# Sheet1.net
KiCad netlist of a schematic drawn in Altium Designer
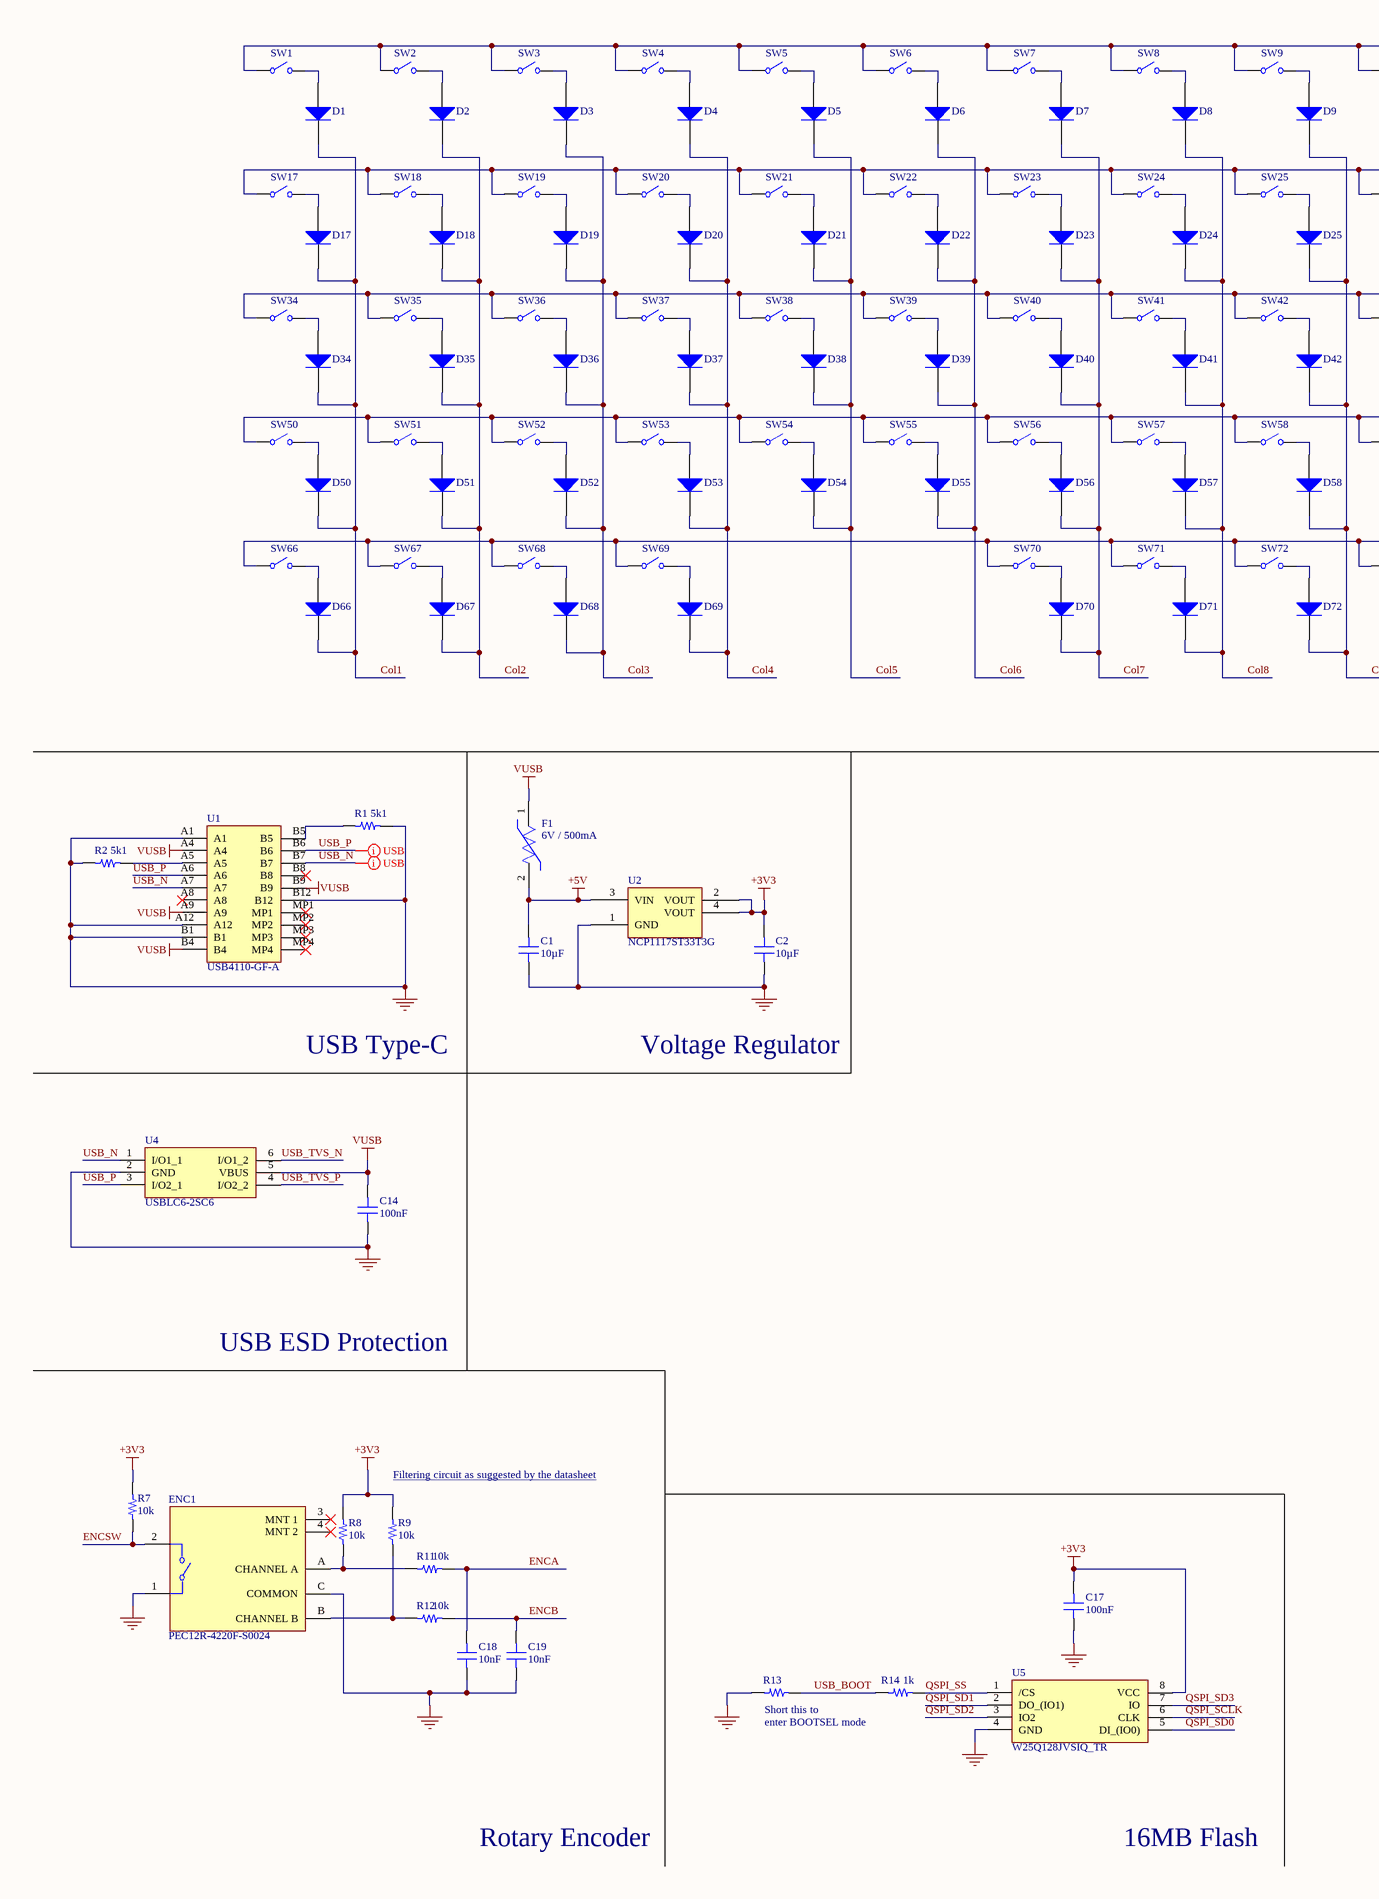
[diagram p0: Sheet1.SchDoc, left]
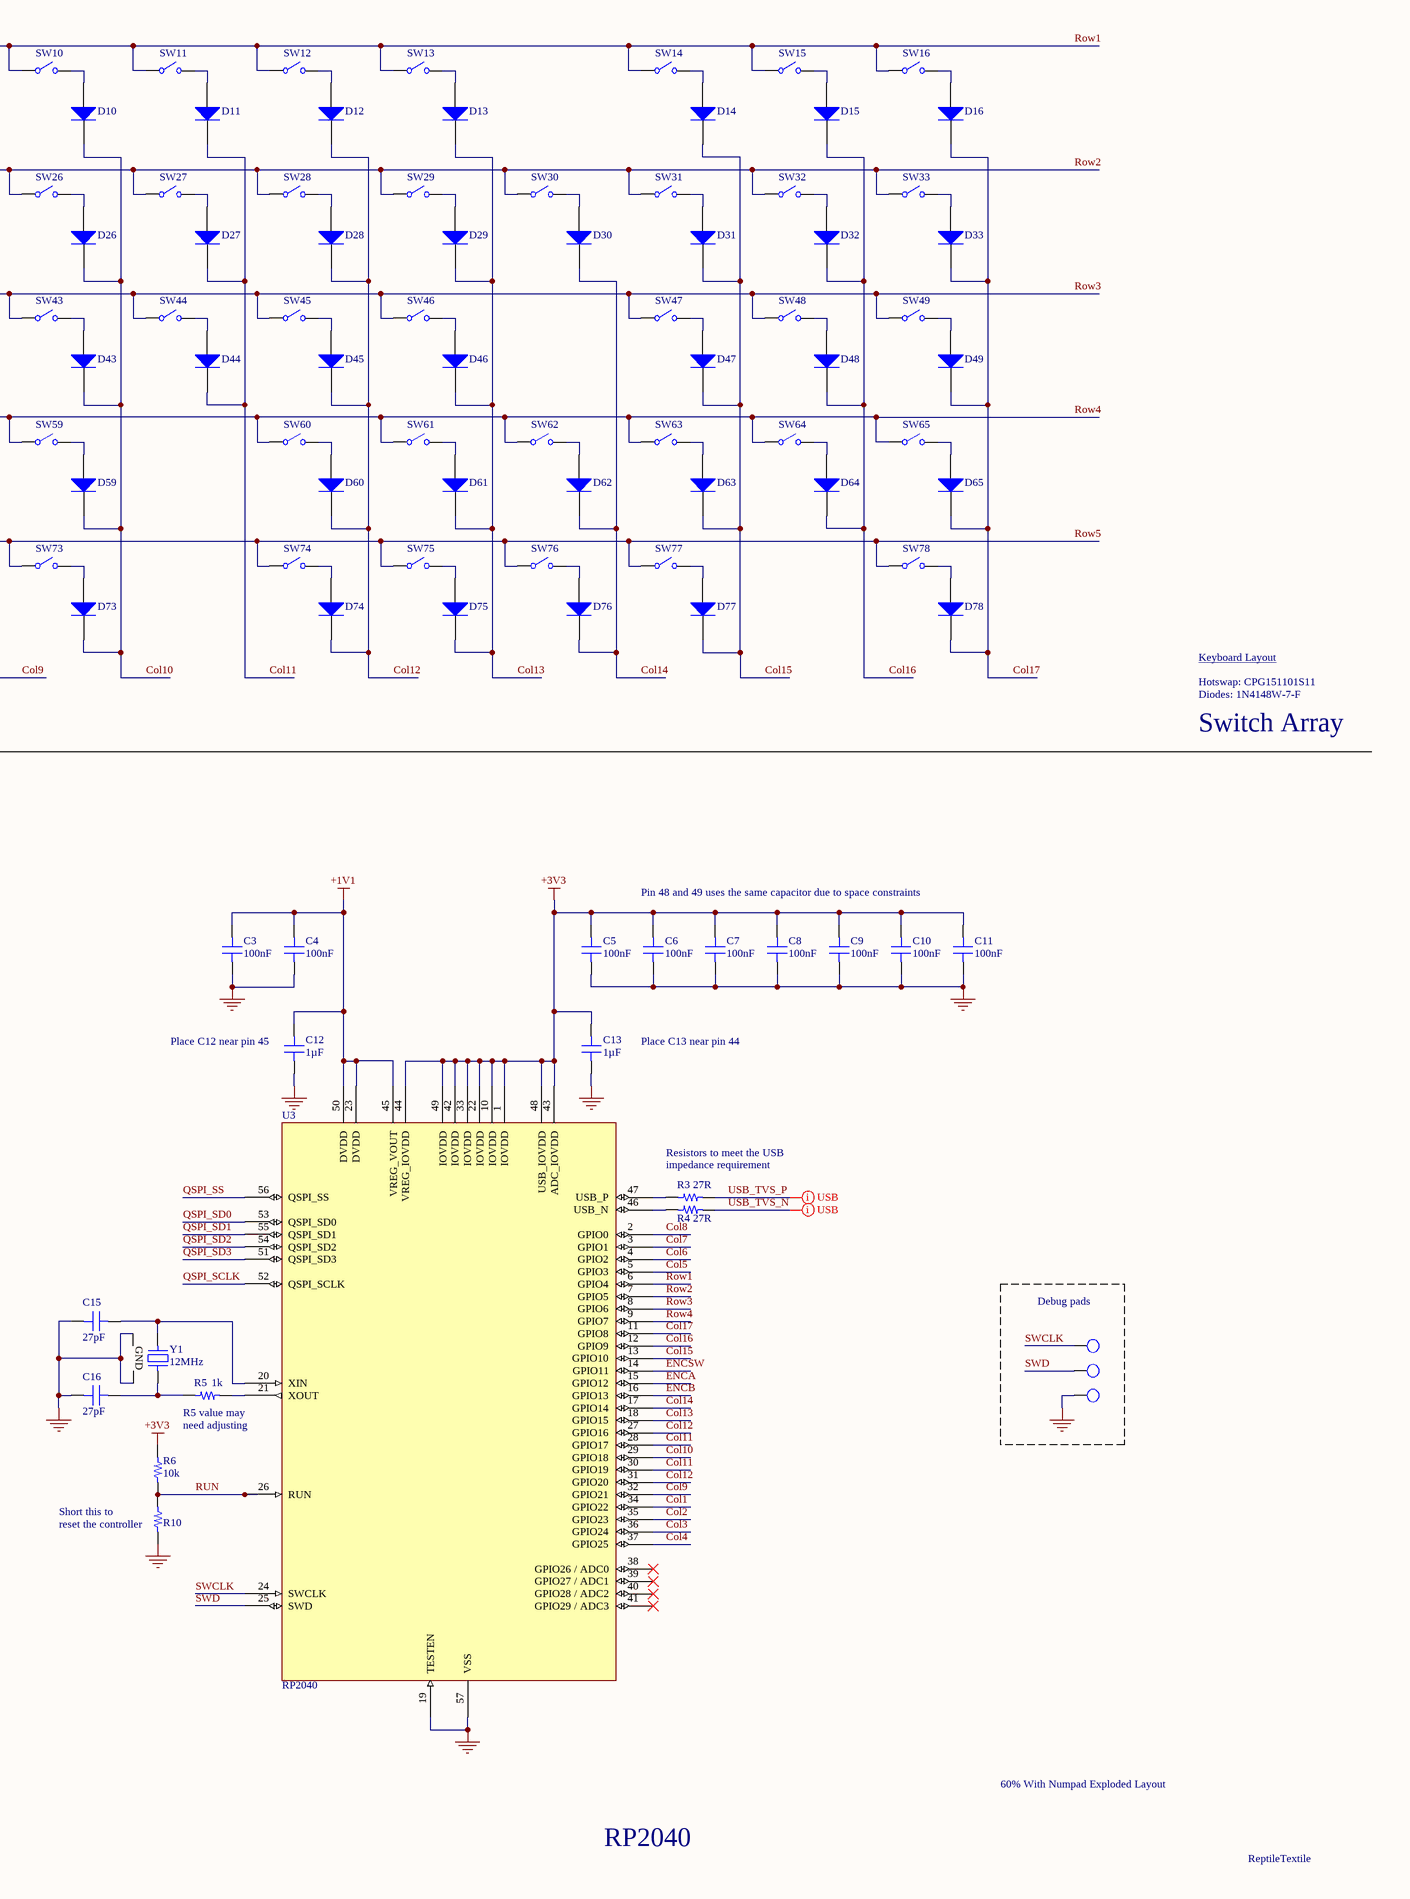
[diagram p1: Sheet1.SchDoc, right]

(export (version "E")
  (design (tool "Eeschema 10.0.6"))
  (components
    (comp (ref "C1")
      (value "10µF")
      (footprint "CAP 0402_1005")
      (description "CAP CER 10UF 10V X5R 0402")
      (fields
        (field (name "PART NUMBER") "CL05A106MP8NUB8")
        (field (name "MANUFACTURER") "Samsung Electro-Mechanics")
      )
      (libsource (lib "Celestial Altium Library") (part "Capacitor"))
    )
    (comp (ref "C2")
      (value "10µF")
      (footprint "CAP 0402_1005")
      (description "CAP CER 10UF 10V X5R 0402")
      (fields
        (field (name "PART NUMBER") "CL05A106MP8NUB8")
        (field (name "MANUFACTURER") "Samsung Electro-Mechanics")
      )
      (libsource (lib "Celestial Altium Library") (part "Capacitor"))
    )
    (comp (ref "C3")
      (value "100nF")
      (footprint "CAP 0402_1005")
      (description "CAP CER 0402 0.1UF 16V X7R 10%")
      (fields (field (name "PART NUMBER") "C0402C104K4RECAUTO") (field (name "MANUFACTURER") "KEMET"))
      (libsource (lib "Celestial Altium Library") (part "Capacitor"))
    )
    (comp (ref "C4")
      (value "100nF")
      (footprint "CAP 0402_1005")
      (description "CAP CER 0402 0.1UF 16V X7R 10%")
      (fields (field (name "PART NUMBER") "C0402C104K4RECAUTO") (field (name "MANUFACTURER") "KEMET"))
      (libsource (lib "Celestial Altium Library") (part "Capacitor"))
    )
    (comp (ref "C5")
      (value "100nF")
      (footprint "CAP 0402_1005")
      (description "CAP CER 0402 0.1UF 16V X7R 10%")
      (fields (field (name "PART NUMBER") "C0402C104K4RECAUTO") (field (name "MANUFACTURER") "KEMET"))
      (libsource (lib "Celestial Altium Library") (part "Capacitor"))
    )
    (comp (ref "C6")
      (value "100nF")
      (footprint "CAP 0402_1005")
      (description "CAP CER 0402 0.1UF 16V X7R 10%")
      (fields (field (name "PART NUMBER") "C0402C104K4RECAUTO") (field (name "MANUFACTURER") "KEMET"))
      (libsource (lib "Celestial Altium Library") (part "Capacitor"))
    )
    (comp (ref "C7")
      (value "100nF")
      (footprint "CAP 0402_1005")
      (description "CAP CER 0402 0.1UF 16V X7R 10%")
      (fields (field (name "PART NUMBER") "C0402C104K4RECAUTO") (field (name "MANUFACTURER") "KEMET"))
      (libsource (lib "Celestial Altium Library") (part "Capacitor"))
    )
    (comp (ref "C8")
      (value "100nF")
      (footprint "CAP 0402_1005")
      (description "CAP CER 0402 0.1UF 16V X7R 10%")
      (fields (field (name "PART NUMBER") "C0402C104K4RECAUTO") (field (name "MANUFACTURER") "KEMET"))
      (libsource (lib "Celestial Altium Library") (part "Capacitor"))
    )
    (comp (ref "C9")
      (value "100nF")
      (footprint "CAP 0402_1005")
      (description "CAP CER 0402 0.1UF 16V X7R 10%")
      (fields (field (name "PART NUMBER") "C0402C104K4RECAUTO") (field (name "MANUFACTURER") "KEMET"))
      (libsource (lib "Celestial Altium Library") (part "Capacitor"))
    )
    (comp (ref "C10")
      (value "100nF")
      (footprint "CAP 0402_1005")
      (description "CAP CER 0402 0.1UF 16V X7R 10%")
      (fields (field (name "PART NUMBER") "C0402C104K4RECAUTO") (field (name "MANUFACTURER") "KEMET"))
      (libsource (lib "Celestial Altium Library") (part "Capacitor"))
    )
    (comp (ref "C11")
      (value "100nF")
      (footprint "CAP 0402_1005")
      (description "CAP CER 0402 0.1UF 16V X7R 10%")
      (fields (field (name "PART NUMBER") "C0402C104K4RECAUTO") (field (name "MANUFACTURER") "KEMET"))
      (libsource (lib "Celestial Altium Library") (part "Capacitor"))
    )
    (comp (ref "C12")
      (value "1µF")
      (footprint "CAP 0402_1005")
      (description "CAP CER 1UF 10V X7S 0402")
      (fields
        (field (name "PART NUMBER") "GRM155C71A105KE11D")
        (field (name "MANUFACTURER") "Murata Electronics")
      )
      (libsource (lib "Celestial Altium Library") (part "Capacitor"))
    )
    (comp (ref "C13")
      (value "1µF")
      (footprint "CAP 0402_1005")
      (description "CAP CER 1UF 10V X7S 0402")
      (fields
        (field (name "PART NUMBER") "GRM155C71A105KE11D")
        (field (name "MANUFACTURER") "Murata Electronics")
      )
      (libsource (lib "Celestial Altium Library") (part "Capacitor"))
    )
    (comp (ref "C14")
      (value "100nF")
      (footprint "CAP 0402_1005")
      (description "CAP CER 0402 0.1UF 16V X7R 10%")
      (fields (field (name "PART NUMBER") "C0402C104K4RECAUTO") (field (name "MANUFACTURER") "KEMET"))
      (libsource (lib "Celestial Altium Library") (part "Capacitor"))
    )
    (comp (ref "C15")
      (value "27pF")
      (footprint "CAP 0402_1005")
      (description "CAP CER 27PF 25V NP0 0402")
      (fields (field (name "PART NUMBER") "C0402C270J3GAC7867") (field (name "MANUFACTURER") "KEMET"))
      (libsource (lib "Celestial Altium Library") (part "Capacitor"))
    )
    (comp (ref "C16")
      (value "27pF")
      (footprint "CAP 0402_1005")
      (description "CAP CER 27PF 25V NP0 0402")
      (fields (field (name "PART NUMBER") "C0402C270J3GAC7867") (field (name "MANUFACTURER") "KEMET"))
      (libsource (lib "Celestial Altium Library") (part "Capacitor"))
    )
    (comp (ref "C17")
      (value "100nF")
      (footprint "CAP 0402_1005")
      (description "CAP CER 0402 0.1UF 16V X7R 10%")
      (fields (field (name "PART NUMBER") "C0402C104K4RECAUTO") (field (name "MANUFACTURER") "KEMET"))
      (libsource (lib "Celestial Altium Library") (part "Capacitor"))
    )
    (comp (ref "C18")
      (value "10nF")
      (footprint "CAP 0402_1005")
      (description "CAP CER 0402 10NF 50V X7R 5%")
      (fields (field (name "PART NUMBER") "C0402C103J5RECAUTO") (field (name "MANUFACTURER") "KEMET"))
      (libsource (lib "Celestial Altium Library") (part "Capacitor"))
    )
    (comp (ref "C19")
      (value "10nF")
      (footprint "CAP 0402_1005")
      (description "CAP CER 0402 10NF 50V X7R 5%")
      (fields (field (name "PART NUMBER") "C0402C103J5RECAUTO") (field (name "MANUFACTURER") "KEMET"))
      (libsource (lib "Celestial Altium Library") (part "Capacitor"))
    )
    (comp (ref "D1")
      (value "1N4148W-7-F")
      (footprint "DIOD-SOD123-2_V")
      (description "Fast Switching Diode, 100 V, 0.15 A, -65 to 150 degC, 2-Pin?SOD123, RoHS, Tape and Reel")
      (fields (field (name "MANUFACTURER") "DiodesIncorporated"))
      (libsource (lib "Altium Content Vault") (part "D-AK-2"))
    )
    (comp (ref "D2")
      (value "1N4148W-7-F")
      (footprint "DIOD-SOD123-2_V")
      (description "Fast Switching Diode, 100 V, 0.15 A, -65 to 150 degC, 2-Pin?SOD123, RoHS, Tape and Reel")
      (fields (field (name "MANUFACTURER") "DiodesIncorporated"))
      (libsource (lib "Altium Content Vault") (part "D-AK-2"))
    )
    (comp (ref "D3")
      (value "1N4148W-7-F")
      (footprint "DIOD-SOD123-2_V")
      (description "Fast Switching Diode, 100 V, 0.15 A, -65 to 150 degC, 2-Pin?SOD123, RoHS, Tape and Reel")
      (fields (field (name "MANUFACTURER") "DiodesIncorporated"))
      (libsource (lib "Altium Content Vault") (part "D-AK-2"))
    )
    (comp (ref "D4")
      (value "1N4148W-7-F")
      (footprint "DIOD-SOD123-2_V")
      (description "Fast Switching Diode, 100 V, 0.15 A, -65 to 150 degC, 2-Pin?SOD123, RoHS, Tape and Reel")
      (fields (field (name "MANUFACTURER") "DiodesIncorporated"))
      (libsource (lib "Altium Content Vault") (part "D-AK-2"))
    )
    (comp (ref "D5")
      (value "1N4148W-7-F")
      (footprint "DIOD-SOD123-2_V")
      (description "Fast Switching Diode, 100 V, 0.15 A, -65 to 150 degC, 2-Pin?SOD123, RoHS, Tape and Reel")
      (fields (field (name "MANUFACTURER") "DiodesIncorporated"))
      (libsource (lib "Altium Content Vault") (part "D-AK-2"))
    )
    (comp (ref "D6")
      (value "1N4148W-7-F")
      (footprint "DIOD-SOD123-2_V")
      (description "Fast Switching Diode, 100 V, 0.15 A, -65 to 150 degC, 2-Pin?SOD123, RoHS, Tape and Reel")
      (fields (field (name "MANUFACTURER") "DiodesIncorporated"))
      (libsource (lib "Altium Content Vault") (part "D-AK-2"))
    )
    (comp (ref "D7")
      (value "1N4148W-7-F")
      (footprint "DIOD-SOD123-2_V")
      (description "Fast Switching Diode, 100 V, 0.15 A, -65 to 150 degC, 2-Pin?SOD123, RoHS, Tape and Reel")
      (fields (field (name "MANUFACTURER") "DiodesIncorporated"))
      (libsource (lib "Altium Content Vault") (part "D-AK-2"))
    )
    (comp (ref "D8")
      (value "1N4148W-7-F")
      (footprint "DIOD-SOD123-2_V")
      (description "Fast Switching Diode, 100 V, 0.15 A, -65 to 150 degC, 2-Pin?SOD123, RoHS, Tape and Reel")
      (fields (field (name "MANUFACTURER") "DiodesIncorporated"))
      (libsource (lib "Altium Content Vault") (part "D-AK-2"))
    )
    (comp (ref "D9")
      (value "1N4148W-7-F")
      (footprint "DIOD-SOD123-2_V")
      (description "Fast Switching Diode, 100 V, 0.15 A, -65 to 150 degC, 2-Pin?SOD123, RoHS, Tape and Reel")
      (fields (field (name "MANUFACTURER") "DiodesIncorporated"))
      (libsource (lib "Altium Content Vault") (part "D-AK-2"))
    )
    (comp (ref "D10")
      (value "1N4148W-7-F")
      (footprint "DIOD-SOD123-2_V")
      (description "Fast Switching Diode, 100 V, 0.15 A, -65 to 150 degC, 2-Pin?SOD123, RoHS, Tape and Reel")
      (fields (field (name "MANUFACTURER") "DiodesIncorporated"))
      (libsource (lib "Altium Content Vault") (part "D-AK-2"))
    )
    (comp (ref "D11")
      (value "1N4148W-7-F")
      (footprint "DIOD-SOD123-2_V")
      (description "Fast Switching Diode, 100 V, 0.15 A, -65 to 150 degC, 2-Pin?SOD123, RoHS, Tape and Reel")
      (fields (field (name "MANUFACTURER") "DiodesIncorporated"))
      (libsource (lib "Altium Content Vault") (part "D-AK-2"))
    )
    (comp (ref "D12")
      (value "1N4148W-7-F")
      (footprint "DIOD-SOD123-2_V")
      (description "Fast Switching Diode, 100 V, 0.15 A, -65 to 150 degC, 2-Pin?SOD123, RoHS, Tape and Reel")
      (fields (field (name "MANUFACTURER") "DiodesIncorporated"))
      (libsource (lib "Altium Content Vault") (part "D-AK-2"))
    )
    (comp (ref "D13")
      (value "1N4148W-7-F")
      (footprint "DIOD-SOD123-2_V")
      (description "Fast Switching Diode, 100 V, 0.15 A, -65 to 150 degC, 2-Pin?SOD123, RoHS, Tape and Reel")
      (fields (field (name "MANUFACTURER") "DiodesIncorporated"))
      (libsource (lib "Altium Content Vault") (part "D-AK-2"))
    )
    (comp (ref "D14")
      (value "1N4148W-7-F")
      (footprint "DIOD-SOD123-2_V")
      (description "Fast Switching Diode, 100 V, 0.15 A, -65 to 150 degC, 2-Pin?SOD123, RoHS, Tape and Reel")
      (fields (field (name "MANUFACTURER") "DiodesIncorporated"))
      (libsource (lib "Altium Content Vault") (part "D-AK-2"))
    )
    (comp (ref "D15")
      (value "1N4148W-7-F")
      (footprint "DIOD-SOD123-2_V")
      (description "Fast Switching Diode, 100 V, 0.15 A, -65 to 150 degC, 2-Pin?SOD123, RoHS, Tape and Reel")
      (fields (field (name "MANUFACTURER") "DiodesIncorporated"))
      (libsource (lib "Altium Content Vault") (part "D-AK-2"))
    )
    (comp (ref "D16")
      (value "1N4148W-7-F")
      (footprint "DIOD-SOD123-2_V")
      (description "Fast Switching Diode, 100 V, 0.15 A, -65 to 150 degC, 2-Pin?SOD123, RoHS, Tape and Reel")
      (fields (field (name "MANUFACTURER") "DiodesIncorporated"))
      (libsource (lib "Altium Content Vault") (part "D-AK-2"))
    )
    (comp (ref "D17")
      (value "1N4148W-7-F")
      (footprint "DIOD-SOD123-2_V")
      (description "Fast Switching Diode, 100 V, 0.15 A, -65 to 150 degC, 2-Pin?SOD123, RoHS, Tape and Reel")
      (fields (field (name "MANUFACTURER") "DiodesIncorporated"))
      (libsource (lib "Altium Content Vault") (part "D-AK-2"))
    )
    (comp (ref "D18")
      (value "1N4148W-7-F")
      (footprint "DIOD-SOD123-2_V")
      (description "Fast Switching Diode, 100 V, 0.15 A, -65 to 150 degC, 2-Pin?SOD123, RoHS, Tape and Reel")
      (fields (field (name "MANUFACTURER") "DiodesIncorporated"))
      (libsource (lib "Altium Content Vault") (part "D-AK-2"))
    )
    (comp (ref "D19")
      (value "1N4148W-7-F")
      (footprint "DIOD-SOD123-2_V")
      (description "Fast Switching Diode, 100 V, 0.15 A, -65 to 150 degC, 2-Pin?SOD123, RoHS, Tape and Reel")
      (fields (field (name "MANUFACTURER") "DiodesIncorporated"))
      (libsource (lib "Altium Content Vault") (part "D-AK-2"))
    )
    (comp (ref "D20")
      (value "1N4148W-7-F")
      (footprint "DIOD-SOD123-2_V")
      (description "Fast Switching Diode, 100 V, 0.15 A, -65 to 150 degC, 2-Pin?SOD123, RoHS, Tape and Reel")
      (fields (field (name "MANUFACTURER") "DiodesIncorporated"))
      (libsource (lib "Altium Content Vault") (part "D-AK-2"))
    )
    (comp (ref "D21")
      (value "1N4148W-7-F")
      (footprint "DIOD-SOD123-2_V")
      (description "Fast Switching Diode, 100 V, 0.15 A, -65 to 150 degC, 2-Pin?SOD123, RoHS, Tape and Reel")
      (fields (field (name "MANUFACTURER") "DiodesIncorporated"))
      (libsource (lib "Altium Content Vault") (part "D-AK-2"))
    )
    (comp (ref "D22")
      (value "1N4148W-7-F")
      (footprint "DIOD-SOD123-2_V")
      (description "Fast Switching Diode, 100 V, 0.15 A, -65 to 150 degC, 2-Pin?SOD123, RoHS, Tape and Reel")
      (fields (field (name "MANUFACTURER") "DiodesIncorporated"))
      (libsource (lib "Altium Content Vault") (part "D-AK-2"))
    )
    (comp (ref "D23")
      (value "1N4148W-7-F")
      (footprint "DIOD-SOD123-2_V")
      (description "Fast Switching Diode, 100 V, 0.15 A, -65 to 150 degC, 2-Pin?SOD123, RoHS, Tape and Reel")
      (fields (field (name "MANUFACTURER") "DiodesIncorporated"))
      (libsource (lib "Altium Content Vault") (part "D-AK-2"))
    )
    (comp (ref "D24")
      (value "1N4148W-7-F")
      (footprint "DIOD-SOD123-2_V")
      (description "Fast Switching Diode, 100 V, 0.15 A, -65 to 150 degC, 2-Pin?SOD123, RoHS, Tape and Reel")
      (fields (field (name "MANUFACTURER") "DiodesIncorporated"))
      (libsource (lib "Altium Content Vault") (part "D-AK-2"))
    )
    (comp (ref "D25")
      (value "1N4148W-7-F")
      (footprint "DIOD-SOD123-2_V")
      (description "Fast Switching Diode, 100 V, 0.15 A, -65 to 150 degC, 2-Pin?SOD123, RoHS, Tape and Reel")
      (fields (field (name "MANUFACTURER") "DiodesIncorporated"))
      (libsource (lib "Altium Content Vault") (part "D-AK-2"))
    )
    (comp (ref "D26")
      (value "1N4148W-7-F")
      (footprint "DIOD-SOD123-2_V")
      (description "Fast Switching Diode, 100 V, 0.15 A, -65 to 150 degC, 2-Pin?SOD123, RoHS, Tape and Reel")
      (fields (field (name "MANUFACTURER") "DiodesIncorporated"))
      (libsource (lib "Altium Content Vault") (part "D-AK-2"))
    )
    (comp (ref "D27")
      (value "1N4148W-7-F")
      (footprint "DIOD-SOD123-2_V")
      (description "Fast Switching Diode, 100 V, 0.15 A, -65 to 150 degC, 2-Pin?SOD123, RoHS, Tape and Reel")
      (fields (field (name "MANUFACTURER") "DiodesIncorporated"))
      (libsource (lib "Altium Content Vault") (part "D-AK-2"))
    )
    (comp (ref "D28")
      (value "1N4148W-7-F")
      (footprint "DIOD-SOD123-2_V")
      (description "Fast Switching Diode, 100 V, 0.15 A, -65 to 150 degC, 2-Pin?SOD123, RoHS, Tape and Reel")
      (fields (field (name "MANUFACTURER") "DiodesIncorporated"))
      (libsource (lib "Altium Content Vault") (part "D-AK-2"))
    )
    (comp (ref "D29")
      (value "1N4148W-7-F")
      (footprint "DIOD-SOD123-2_V")
      (description "Fast Switching Diode, 100 V, 0.15 A, -65 to 150 degC, 2-Pin?SOD123, RoHS, Tape and Reel")
      (fields (field (name "MANUFACTURER") "DiodesIncorporated"))
      (libsource (lib "Altium Content Vault") (part "D-AK-2"))
    )
    (comp (ref "D30")
      (value "1N4148W-7-F")
      (footprint "DIOD-SOD123-2_V")
      (description "Fast Switching Diode, 100 V, 0.15 A, -65 to 150 degC, 2-Pin?SOD123, RoHS, Tape and Reel")
      (fields (field (name "MANUFACTURER") "DiodesIncorporated"))
      (libsource (lib "Altium Content Vault") (part "D-AK-2"))
    )
    (comp (ref "D31")
      (value "1N4148W-7-F")
      (footprint "DIOD-SOD123-2_V")
      (description "Fast Switching Diode, 100 V, 0.15 A, -65 to 150 degC, 2-Pin?SOD123, RoHS, Tape and Reel")
      (fields (field (name "MANUFACTURER") "DiodesIncorporated"))
      (libsource (lib "Altium Content Vault") (part "D-AK-2"))
    )
    (comp (ref "D32")
      (value "1N4148W-7-F")
      (footprint "DIOD-SOD123-2_V")
      (description "Fast Switching Diode, 100 V, 0.15 A, -65 to 150 degC, 2-Pin?SOD123, RoHS, Tape and Reel")
      (fields (field (name "MANUFACTURER") "DiodesIncorporated"))
      (libsource (lib "Altium Content Vault") (part "D-AK-2"))
    )
    (comp (ref "D33")
      (value "1N4148W-7-F")
      (footprint "DIOD-SOD123-2_V")
      (description "Fast Switching Diode, 100 V, 0.15 A, -65 to 150 degC, 2-Pin?SOD123, RoHS, Tape and Reel")
      (fields (field (name "MANUFACTURER") "DiodesIncorporated"))
      (libsource (lib "Altium Content Vault") (part "D-AK-2"))
    )
    (comp (ref "D34")
      (value "1N4148W-7-F")
      (footprint "DIOD-SOD123-2_V")
      (description "Fast Switching Diode, 100 V, 0.15 A, -65 to 150 degC, 2-Pin?SOD123, RoHS, Tape and Reel")
      (fields (field (name "MANUFACTURER") "DiodesIncorporated"))
      (libsource (lib "Altium Content Vault") (part "D-AK-2"))
    )
    (comp (ref "D35")
      (value "1N4148W-7-F")
      (footprint "DIOD-SOD123-2_V")
      (description "Fast Switching Diode, 100 V, 0.15 A, -65 to 150 degC, 2-Pin?SOD123, RoHS, Tape and Reel")
      (fields (field (name "MANUFACTURER") "DiodesIncorporated"))
      (libsource (lib "Altium Content Vault") (part "D-AK-2"))
    )
    (comp (ref "D36")
      (value "1N4148W-7-F")
      (footprint "DIOD-SOD123-2_V")
      (description "Fast Switching Diode, 100 V, 0.15 A, -65 to 150 degC, 2-Pin?SOD123, RoHS, Tape and Reel")
      (fields (field (name "MANUFACTURER") "DiodesIncorporated"))
      (libsource (lib "Altium Content Vault") (part "D-AK-2"))
    )
    (comp (ref "D37")
      (value "1N4148W-7-F")
      (footprint "DIOD-SOD123-2_V")
      (description "Fast Switching Diode, 100 V, 0.15 A, -65 to 150 degC, 2-Pin?SOD123, RoHS, Tape and Reel")
      (fields (field (name "MANUFACTURER") "DiodesIncorporated"))
      (libsource (lib "Altium Content Vault") (part "D-AK-2"))
    )
    (comp (ref "D38")
      (value "1N4148W-7-F")
      (footprint "DIOD-SOD123-2_V")
      (description "Fast Switching Diode, 100 V, 0.15 A, -65 to 150 degC, 2-Pin?SOD123, RoHS, Tape and Reel")
      (fields (field (name "MANUFACTURER") "DiodesIncorporated"))
      (libsource (lib "Altium Content Vault") (part "D-AK-2"))
    )
    (comp (ref "D39")
      (value "1N4148W-7-F")
      (footprint "DIOD-SOD123-2_V")
      (description "Fast Switching Diode, 100 V, 0.15 A, -65 to 150 degC, 2-Pin?SOD123, RoHS, Tape and Reel")
      (fields (field (name "MANUFACTURER") "DiodesIncorporated"))
      (libsource (lib "Altium Content Vault") (part "D-AK-2"))
    )
    (comp (ref "D40")
      (value "1N4148W-7-F")
      (footprint "DIOD-SOD123-2_V")
      (description "Fast Switching Diode, 100 V, 0.15 A, -65 to 150 degC, 2-Pin?SOD123, RoHS, Tape and Reel")
      (fields (field (name "MANUFACTURER") "DiodesIncorporated"))
      (libsource (lib "Altium Content Vault") (part "D-AK-2"))
    )
    (comp (ref "D41")
      (value "1N4148W-7-F")
      (footprint "DIOD-SOD123-2_V")
      (description "Fast Switching Diode, 100 V, 0.15 A, -65 to 150 degC, 2-Pin?SOD123, RoHS, Tape and Reel")
      (fields (field (name "MANUFACTURER") "DiodesIncorporated"))
      (libsource (lib "Altium Content Vault") (part "D-AK-2"))
    )
    (comp (ref "D42")
      (value "1N4148W-7-F")
      (footprint "DIOD-SOD123-2_V")
      (description "Fast Switching Diode, 100 V, 0.15 A, -65 to 150 degC, 2-Pin?SOD123, RoHS, Tape and Reel")
      (fields (field (name "MANUFACTURER") "DiodesIncorporated"))
      (libsource (lib "Altium Content Vault") (part "D-AK-2"))
    )
    (comp (ref "D43")
      (value "1N4148W-7-F")
      (footprint "DIOD-SOD123-2_V")
      (description "Fast Switching Diode, 100 V, 0.15 A, -65 to 150 degC, 2-Pin?SOD123, RoHS, Tape and Reel")
      (fields (field (name "MANUFACTURER") "DiodesIncorporated"))
      (libsource (lib "Altium Content Vault") (part "D-AK-2"))
    )
    (comp (ref "D44")
      (value "1N4148W-7-F")
      (footprint "DIOD-SOD123-2_V")
      (description "Fast Switching Diode, 100 V, 0.15 A, -65 to 150 degC, 2-Pin?SOD123, RoHS, Tape and Reel")
      (fields (field (name "MANUFACTURER") "DiodesIncorporated"))
      (libsource (lib "Altium Content Vault") (part "D-AK-2"))
    )
    (comp (ref "D45")
      (value "1N4148W-7-F")
      (footprint "DIOD-SOD123-2_V")
      (description "Fast Switching Diode, 100 V, 0.15 A, -65 to 150 degC, 2-Pin?SOD123, RoHS, Tape and Reel")
      (fields (field (name "MANUFACTURER") "DiodesIncorporated"))
      (libsource (lib "Altium Content Vault") (part "D-AK-2"))
    )
    (comp (ref "D46")
      (value "1N4148W-7-F")
      (footprint "DIOD-SOD123-2_V")
      (description "Fast Switching Diode, 100 V, 0.15 A, -65 to 150 degC, 2-Pin?SOD123, RoHS, Tape and Reel")
      (fields (field (name "MANUFACTURER") "DiodesIncorporated"))
      (libsource (lib "Altium Content Vault") (part "D-AK-2"))
    )
    (comp (ref "D47")
      (value "1N4148W-7-F")
      (footprint "DIOD-SOD123-2_V")
      (description "Fast Switching Diode, 100 V, 0.15 A, -65 to 150 degC, 2-Pin?SOD123, RoHS, Tape and Reel")
      (fields (field (name "MANUFACTURER") "DiodesIncorporated"))
      (libsource (lib "Altium Content Vault") (part "D-AK-2"))
    )
    (comp (ref "D48")
      (value "1N4148W-7-F")
      (footprint "DIOD-SOD123-2_V")
      (description "Fast Switching Diode, 100 V, 0.15 A, -65 to 150 degC, 2-Pin?SOD123, RoHS, Tape and Reel")
      (fields (field (name "MANUFACTURER") "DiodesIncorporated"))
      (libsource (lib "Altium Content Vault") (part "D-AK-2"))
    )
    (comp (ref "D49")
      (value "1N4148W-7-F")
      (footprint "DIOD-SOD123-2_V")
      (description "Fast Switching Diode, 100 V, 0.15 A, -65 to 150 degC, 2-Pin?SOD123, RoHS, Tape and Reel")
      (fields (field (name "MANUFACTURER") "DiodesIncorporated"))
      (libsource (lib "Altium Content Vault") (part "D-AK-2"))
    )
    (comp (ref "D50")
      (value "1N4148W-7-F")
      (footprint "DIOD-SOD123-2_V")
      (description "Fast Switching Diode, 100 V, 0.15 A, -65 to 150 degC, 2-Pin?SOD123, RoHS, Tape and Reel")
      (fields (field (name "MANUFACTURER") "DiodesIncorporated"))
      (libsource (lib "Altium Content Vault") (part "D-AK-2"))
    )
    (comp (ref "D51")
      (value "1N4148W-7-F")
      (footprint "DIOD-SOD123-2_V")
      (description "Fast Switching Diode, 100 V, 0.15 A, -65 to 150 degC, 2-Pin?SOD123, RoHS, Tape and Reel")
      (fields (field (name "MANUFACTURER") "DiodesIncorporated"))
      (libsource (lib "Altium Content Vault") (part "D-AK-2"))
    )
    (comp (ref "D52")
      (value "1N4148W-7-F")
      (footprint "DIOD-SOD123-2_V")
      (description "Fast Switching Diode, 100 V, 0.15 A, -65 to 150 degC, 2-Pin?SOD123, RoHS, Tape and Reel")
      (fields (field (name "MANUFACTURER") "DiodesIncorporated"))
      (libsource (lib "Altium Content Vault") (part "D-AK-2"))
    )
    (comp (ref "D53")
      (value "1N4148W-7-F")
      (footprint "DIOD-SOD123-2_V")
      (description "Fast Switching Diode, 100 V, 0.15 A, -65 to 150 degC, 2-Pin?SOD123, RoHS, Tape and Reel")
      (fields (field (name "MANUFACTURER") "DiodesIncorporated"))
      (libsource (lib "Altium Content Vault") (part "D-AK-2"))
    )
    (comp (ref "D54")
      (value "1N4148W-7-F")
      (footprint "DIOD-SOD123-2_V")
      (description "Fast Switching Diode, 100 V, 0.15 A, -65 to 150 degC, 2-Pin?SOD123, RoHS, Tape and Reel")
      (fields (field (name "MANUFACTURER") "DiodesIncorporated"))
      (libsource (lib "Altium Content Vault") (part "D-AK-2"))
    )
    (comp (ref "D55")
      (value "1N4148W-7-F")
      (footprint "DIOD-SOD123-2_V")
      (description "Fast Switching Diode, 100 V, 0.15 A, -65 to 150 degC, 2-Pin?SOD123, RoHS, Tape and Reel")
      (fields (field (name "MANUFACTURER") "DiodesIncorporated"))
      (libsource (lib "Altium Content Vault") (part "D-AK-2"))
    )
    (comp (ref "D56")
      (value "1N4148W-7-F")
      (footprint "DIOD-SOD123-2_V")
      (description "Fast Switching Diode, 100 V, 0.15 A, -65 to 150 degC, 2-Pin?SOD123, RoHS, Tape and Reel")
      (fields (field (name "MANUFACTURER") "DiodesIncorporated"))
      (libsource (lib "Altium Content Vault") (part "D-AK-2"))
    )
    (comp (ref "D57")
      (value "1N4148W-7-F")
      (footprint "DIOD-SOD123-2_V")
      (description "Fast Switching Diode, 100 V, 0.15 A, -65 to 150 degC, 2-Pin?SOD123, RoHS, Tape and Reel")
      (fields (field (name "MANUFACTURER") "DiodesIncorporated"))
      (libsource (lib "Altium Content Vault") (part "D-AK-2"))
    )
    (comp (ref "D58")
      (value "1N4148W-7-F")
      (footprint "DIOD-SOD123-2_V")
      (description "Fast Switching Diode, 100 V, 0.15 A, -65 to 150 degC, 2-Pin?SOD123, RoHS, Tape and Reel")
      (fields (field (name "MANUFACTURER") "DiodesIncorporated"))
      (libsource (lib "Altium Content Vault") (part "D-AK-2"))
    )
    (comp (ref "D59")
      (value "1N4148W-7-F")
      (footprint "DIOD-SOD123-2_V")
      (description "Fast Switching Diode, 100 V, 0.15 A, -65 to 150 degC, 2-Pin?SOD123, RoHS, Tape and Reel")
      (fields (field (name "MANUFACTURER") "DiodesIncorporated"))
      (libsource (lib "Altium Content Vault") (part "D-AK-2"))
    )
    (comp (ref "D60")
      (value "1N4148W-7-F")
      (footprint "DIOD-SOD123-2_V")
      (description "Fast Switching Diode, 100 V, 0.15 A, -65 to 150 degC, 2-Pin?SOD123, RoHS, Tape and Reel")
      (fields (field (name "MANUFACTURER") "DiodesIncorporated"))
      (libsource (lib "Altium Content Vault") (part "D-AK-2"))
    )
    (comp (ref "D61")
      (value "1N4148W-7-F")
      (footprint "DIOD-SOD123-2_V")
      (description "Fast Switching Diode, 100 V, 0.15 A, -65 to 150 degC, 2-Pin?SOD123, RoHS, Tape and Reel")
      (fields (field (name "MANUFACTURER") "DiodesIncorporated"))
      (libsource (lib "Altium Content Vault") (part "D-AK-2"))
    )
    (comp (ref "D62")
      (value "1N4148W-7-F")
      (footprint "DIOD-SOD123-2_V")
      (description "Fast Switching Diode, 100 V, 0.15 A, -65 to 150 degC, 2-Pin?SOD123, RoHS, Tape and Reel")
      (fields (field (name "MANUFACTURER") "DiodesIncorporated"))
      (libsource (lib "Altium Content Vault") (part "D-AK-2"))
    )
    (comp (ref "D63")
      (value "1N4148W-7-F")
      (footprint "DIOD-SOD123-2_V")
      (description "Fast Switching Diode, 100 V, 0.15 A, -65 to 150 degC, 2-Pin?SOD123, RoHS, Tape and Reel")
      (fields (field (name "MANUFACTURER") "DiodesIncorporated"))
      (libsource (lib "Altium Content Vault") (part "D-AK-2"))
    )
    (comp (ref "D64")
      (value "1N4148W-7-F")
      (footprint "DIOD-SOD123-2_V")
      (description "Fast Switching Diode, 100 V, 0.15 A, -65 to 150 degC, 2-Pin?SOD123, RoHS, Tape and Reel")
      (fields (field (name "MANUFACTURER") "DiodesIncorporated"))
      (libsource (lib "Altium Content Vault") (part "D-AK-2"))
    )
    (comp (ref "D65")
      (value "1N4148W-7-F")
      (footprint "DIOD-SOD123-2_V")
      (description "Fast Switching Diode, 100 V, 0.15 A, -65 to 150 degC, 2-Pin?SOD123, RoHS, Tape and Reel")
      (fields (field (name "MANUFACTURER") "DiodesIncorporated"))
      (libsource (lib "Altium Content Vault") (part "D-AK-2"))
    )
    (comp (ref "D66")
      (value "1N4148W-7-F")
      (footprint "DIOD-SOD123-2_V")
      (description "Fast Switching Diode, 100 V, 0.15 A, -65 to 150 degC, 2-Pin?SOD123, RoHS, Tape and Reel")
      (fields (field (name "MANUFACTURER") "DiodesIncorporated"))
      (libsource (lib "Altium Content Vault") (part "D-AK-2"))
    )
    (comp (ref "D67")
      (value "1N4148W-7-F")
      (footprint "DIOD-SOD123-2_V")
      (description "Fast Switching Diode, 100 V, 0.15 A, -65 to 150 degC, 2-Pin?SOD123, RoHS, Tape and Reel")
      (fields (field (name "MANUFACTURER") "DiodesIncorporated"))
      (libsource (lib "Altium Content Vault") (part "D-AK-2"))
    )
    (comp (ref "D68")
      (value "1N4148W-7-F")
      (footprint "DIOD-SOD123-2_V")
      (description "Fast Switching Diode, 100 V, 0.15 A, -65 to 150 degC, 2-Pin?SOD123, RoHS, Tape and Reel")
      (fields (field (name "MANUFACTURER") "DiodesIncorporated"))
      (libsource (lib "Altium Content Vault") (part "D-AK-2"))
    )
    (comp (ref "D69")
      (value "1N4148W-7-F")
      (footprint "DIOD-SOD123-2_V")
      (description "Fast Switching Diode, 100 V, 0.15 A, -65 to 150 degC, 2-Pin?SOD123, RoHS, Tape and Reel")
      (fields (field (name "MANUFACTURER") "DiodesIncorporated"))
      (libsource (lib "Altium Content Vault") (part "D-AK-2"))
    )
    (comp (ref "D70")
      (value "1N4148W-7-F")
      (footprint "DIOD-SOD123-2_V")
      (description "Fast Switching Diode, 100 V, 0.15 A, -65 to 150 degC, 2-Pin?SOD123, RoHS, Tape and Reel")
      (fields (field (name "MANUFACTURER") "DiodesIncorporated"))
      (libsource (lib "Altium Content Vault") (part "D-AK-2"))
    )
    (comp (ref "D71")
      (value "1N4148W-7-F")
      (footprint "DIOD-SOD123-2_V")
      (description "Fast Switching Diode, 100 V, 0.15 A, -65 to 150 degC, 2-Pin?SOD123, RoHS, Tape and Reel")
      (fields (field (name "MANUFACTURER") "DiodesIncorporated"))
      (libsource (lib "Altium Content Vault") (part "D-AK-2"))
    )
    (comp (ref "D72")
      (value "1N4148W-7-F")
      (footprint "DIOD-SOD123-2_V")
      (description "Fast Switching Diode, 100 V, 0.15 A, -65 to 150 degC, 2-Pin?SOD123, RoHS, Tape and Reel")
      (fields (field (name "MANUFACTURER") "DiodesIncorporated"))
      (libsource (lib "Altium Content Vault") (part "D-AK-2"))
    )
    (comp (ref "D73")
      (value "1N4148W-7-F")
      (footprint "DIOD-SOD123-2_V")
      (description "Fast Switching Diode, 100 V, 0.15 A, -65 to 150 degC, 2-Pin?SOD123, RoHS, Tape and Reel")
      (fields (field (name "MANUFACTURER") "DiodesIncorporated"))
      (libsource (lib "Altium Content Vault") (part "D-AK-2"))
    )
    (comp (ref "D74")
      (value "1N4148W-7-F")
      (footprint "DIOD-SOD123-2_V")
      (description "Fast Switching Diode, 100 V, 0.15 A, -65 to 150 degC, 2-Pin?SOD123, RoHS, Tape and Reel")
      (fields (field (name "MANUFACTURER") "DiodesIncorporated"))
      (libsource (lib "Altium Content Vault") (part "D-AK-2"))
    )
    (comp (ref "D75")
      (value "1N4148W-7-F")
      (footprint "DIOD-SOD123-2_V")
      (description "Fast Switching Diode, 100 V, 0.15 A, -65 to 150 degC, 2-Pin?SOD123, RoHS, Tape and Reel")
      (fields (field (name "MANUFACTURER") "DiodesIncorporated"))
      (libsource (lib "Altium Content Vault") (part "D-AK-2"))
    )
    (comp (ref "D76")
      (value "1N4148W-7-F")
      (footprint "DIOD-SOD123-2_V")
      (description "Fast Switching Diode, 100 V, 0.15 A, -65 to 150 degC, 2-Pin?SOD123, RoHS, Tape and Reel")
      (fields (field (name "MANUFACTURER") "DiodesIncorporated"))
      (libsource (lib "Altium Content Vault") (part "D-AK-2"))
    )
    (comp (ref "D77")
      (value "1N4148W-7-F")
      (footprint "DIOD-SOD123-2_V")
      (description "Fast Switching Diode, 100 V, 0.15 A, -65 to 150 degC, 2-Pin?SOD123, RoHS, Tape and Reel")
      (fields (field (name "MANUFACTURER") "DiodesIncorporated"))
      (libsource (lib "Altium Content Vault") (part "D-AK-2"))
    )
    (comp (ref "D78")
      (value "1N4148W-7-F")
      (footprint "DIOD-SOD123-2_V")
      (description "Fast Switching Diode, 100 V, 0.15 A, -65 to 150 degC, 2-Pin?SOD123, RoHS, Tape and Reel")
      (fields (field (name "MANUFACTURER") "DiodesIncorporated"))
      (libsource (lib "Altium Content Vault") (part "D-AK-2"))
    )
    (comp (ref "ENC1")
      (value "PEC12R-4220F-S0024")
      (footprint "FP-PEC12R-4220F-S0024-MFG")
      (description "ROTARY ENCODER MECHANICAL 24PPR")
      (libsource (lib "Altium Content Vault") (part "94c173c7df275f4241826ab5d869309"))
    )
    (comp (ref "F1")
      (value "6V / 500mA")
      (footprint "FP-MF-PSMF-MFG")
      (description "PTC RESET FUSE 6V 500MA 0805")
      (fields
        (field (name "MANUFACTURER PART NUMBER") "MF-PSMF050X-2")
        (field (name "MANUFACTURER") "Bourns Inc.")
      )
      (libsource (lib "Altium Content Vault") (part "fdf083d5f6389a9a1c4e51137f46658"))
    )
    (comp (ref "J1") (value "Pad") (footprint "Square_Pad") (libsource (lib "OnatLib") (part "Pad")))
    (comp (ref "J2") (value "Pad") (footprint "Square_Pad") (libsource (lib "OnatLib") (part "Pad")))
    (comp (ref "J3") (value "Pad") (footprint "Square_Pad") (libsource (lib "OnatLib") (part "Pad")))
    (comp (ref "R1")
      (value "5k1")
      (footprint "RES 0402_1005")
      (description "RES 5.1K OHM 5% 1/16W 0402")
      (fields (field (name "PART NUMBER") "RC0402JR-075K1L") (field (name "MANUFACTURER") "Yageo"))
      (libsource (lib "Celestial Altium Library") (part "Resistor"))
    )
    (comp (ref "R2")
      (value "5k1")
      (footprint "RES 0402_1005")
      (description "RES 5.1K OHM 5% 1/16W 0402")
      (fields (field (name "PART NUMBER") "RC0402JR-075K1L") (field (name "MANUFACTURER") "Yageo"))
      (libsource (lib "Celestial Altium Library") (part "Resistor"))
    )
    (comp (ref "R3")
      (value "27R")
      (footprint "RES 0402_1005")
      (description "RES 27 OHM 1% 1/16W 0402")
      (fields (field (name "PART NUMBER") "RC0402FR-0727RL") (field (name "MANUFACTURER") "Yageo"))
      (libsource (lib "Celestial Altium Library") (part "Resistor"))
    )
    (comp (ref "R4")
      (value "27R")
      (footprint "RES 0402_1005")
      (description "RES 27 OHM 1% 1/16W 0402")
      (fields (field (name "PART NUMBER") "RC0402FR-0727RL") (field (name "MANUFACTURER") "Yageo"))
      (libsource (lib "Celestial Altium Library") (part "Resistor"))
    )
    (comp (ref "R5")
      (value "1k")
      (footprint "RES 0402_1005")
      (description "RES SMD 1K OHM 0.1% 1/16W 0402")
      (fields (field (name "PART NUMBER") "AT0402BRD071KL") (field (name "MANUFACTURER") "Yageo"))
      (libsource (lib "Celestial Altium Library") (part "Resistor"))
    )
    (comp (ref "R6")
      (value "10k")
      (footprint "RES 0402_1005")
      (description "RES 10K OHM 0.1% 1/16W 0402")
      (fields (field (name "PART NUMBER") "TNPW040210K0BETD") (field (name "MANUFACTURER") "Vishay Dale"))
      (libsource (lib "Celestial Altium Library") (part "Resistor"))
    )
    (comp (ref "R7")
      (value "10k")
      (footprint "RES 0402_1005")
      (description "RES 10K OHM 0.1% 1/16W 0402")
      (fields (field (name "PART NUMBER") "TNPW040210K0BETD") (field (name "MANUFACTURER") "Vishay Dale"))
      (libsource (lib "Celestial Altium Library") (part "Resistor"))
    )
    (comp (ref "R8")
      (value "10k")
      (footprint "RES 0402_1005")
      (description "RES 10K OHM 0.1% 1/16W 0402")
      (fields (field (name "PART NUMBER") "TNPW040210K0BETD") (field (name "MANUFACTURER") "Vishay Dale"))
      (libsource (lib "Celestial Altium Library") (part "Resistor"))
    )
    (comp (ref "R9")
      (value "10k")
      (footprint "RES 0402_1005")
      (description "RES 10K OHM 0.1% 1/16W 0402")
      (fields (field (name "PART NUMBER") "TNPW040210K0BETD") (field (name "MANUFACTURER") "Vishay Dale"))
      (libsource (lib "Celestial Altium Library") (part "Resistor"))
    )
    (comp (ref "R10")
      (value "0")
      (footprint "RES 0402_1005")
      (description "RESA-AS 0402 0R JUMPER 63MW")
      (fields (field (name "PART NUMBER") "CR0402AJ/-000GAS") (field (name "MANUFACTURER") "Bourns Inc."))
      (libsource (lib "Celestial Altium Library") (part "Resistor"))
    )
    (comp (ref "R11")
      (value "10k")
      (footprint "RES 0402_1005")
      (description "RES 10K OHM 0.1% 1/16W 0402")
      (fields (field (name "PART NUMBER") "TNPW040210K0BETD") (field (name "MANUFACTURER") "Vishay Dale"))
      (libsource (lib "Celestial Altium Library") (part "Resistor"))
    )
    (comp (ref "R12")
      (value "10k")
      (footprint "RES 0402_1005")
      (description "RES 10K OHM 0.1% 1/16W 0402")
      (fields (field (name "PART NUMBER") "TNPW040210K0BETD") (field (name "MANUFACTURER") "Vishay Dale"))
      (libsource (lib "Celestial Altium Library") (part "Resistor"))
    )
    (comp (ref "R13")
      (value "0")
      (footprint "RES 0402_1005")
      (description "RESA-AS 0402 0R JUMPER 63MW")
      (fields (field (name "PART NUMBER") "CR0402AJ/-000GAS") (field (name "MANUFACTURER") "Bourns Inc."))
      (libsource (lib "Celestial Altium Library") (part "Resistor"))
    )
    (comp (ref "R14")
      (value "1k")
      (footprint "RES 0402_1005")
      (description "RES SMD 1K OHM 0.1% 1/16W 0402")
      (fields (field (name "PART NUMBER") "AT0402BRD071KL") (field (name "MANUFACTURER") "Yageo"))
      (libsource (lib "Celestial Altium Library") (part "Resistor"))
    )
    (comp (ref "SW1")
      (value "CPG151101S11")
      (footprint "CPG151101S11")
      (libsource (lib "OnatLib") (part "CPG151101S11 - Kailh Hotswap Socket"))
    )
    (comp (ref "SW2")
      (value "CPG151101S11")
      (footprint "CPG151101S11")
      (libsource (lib "OnatLib") (part "CPG151101S11 - Kailh Hotswap Socket"))
    )
    (comp (ref "SW3")
      (value "CPG151101S11")
      (footprint "CPG151101S11")
      (libsource (lib "OnatLib") (part "CPG151101S11 - Kailh Hotswap Socket"))
    )
    (comp (ref "SW4")
      (value "CPG151101S11")
      (footprint "CPG151101S11")
      (libsource (lib "OnatLib") (part "CPG151101S11 - Kailh Hotswap Socket"))
    )
    (comp (ref "SW5")
      (value "CPG151101S11")
      (footprint "CPG151101S11")
      (libsource (lib "OnatLib") (part "CPG151101S11 - Kailh Hotswap Socket"))
    )
    (comp (ref "SW6")
      (value "CPG151101S11")
      (footprint "CPG151101S11")
      (libsource (lib "OnatLib") (part "CPG151101S11 - Kailh Hotswap Socket"))
    )
    (comp (ref "SW7")
      (value "CPG151101S11")
      (footprint "CPG151101S11")
      (libsource (lib "OnatLib") (part "CPG151101S11 - Kailh Hotswap Socket"))
    )
    (comp (ref "SW8")
      (value "CPG151101S11")
      (footprint "CPG151101S11")
      (libsource (lib "OnatLib") (part "CPG151101S11 - Kailh Hotswap Socket"))
    )
    (comp (ref "SW9")
      (value "CPG151101S11")
      (footprint "CPG151101S11")
      (libsource (lib "OnatLib") (part "CPG151101S11 - Kailh Hotswap Socket"))
    )
    (comp (ref "SW10")
      (value "CPG151101S11")
      (footprint "CPG151101S11")
      (libsource (lib "OnatLib") (part "CPG151101S11 - Kailh Hotswap Socket"))
    )
    (comp (ref "SW11")
      (value "CPG151101S11")
      (footprint "CPG151101S11")
      (libsource (lib "OnatLib") (part "CPG151101S11 - Kailh Hotswap Socket"))
    )
    (comp (ref "SW12")
      (value "CPG151101S11")
      (footprint "CPG151101S11")
      (libsource (lib "OnatLib") (part "CPG151101S11 - Kailh Hotswap Socket"))
    )
    (comp (ref "SW13")
      (value "CPG151101S11")
      (footprint "CPG151101S11")
      (libsource (lib "OnatLib") (part "CPG151101S11 - Kailh Hotswap Socket"))
    )
    (comp (ref "SW14")
      (value "CPG151101S11")
      (footprint "CPG151101S11")
      (libsource (lib "OnatLib") (part "CPG151101S11 - Kailh Hotswap Socket"))
    )
    (comp (ref "SW15")
      (value "CPG151101S11")
      (footprint "CPG151101S11")
      (libsource (lib "OnatLib") (part "CPG151101S11 - Kailh Hotswap Socket"))
    )
    (comp (ref "SW16")
      (value "CPG151101S11")
      (footprint "CPG151101S11")
      (libsource (lib "OnatLib") (part "CPG151101S11 - Kailh Hotswap Socket"))
    )
    (comp (ref "SW17")
      (value "CPG151101S11")
      (footprint "CPG151101S11")
      (libsource (lib "OnatLib") (part "CPG151101S11 - Kailh Hotswap Socket"))
    )
    (comp (ref "SW18")
      (value "CPG151101S11")
      (footprint "CPG151101S11")
      (libsource (lib "OnatLib") (part "CPG151101S11 - Kailh Hotswap Socket"))
    )
    (comp (ref "SW19")
      (value "CPG151101S11")
      (footprint "CPG151101S11")
      (libsource (lib "OnatLib") (part "CPG151101S11 - Kailh Hotswap Socket"))
    )
    (comp (ref "SW20")
      (value "CPG151101S11")
      (footprint "CPG151101S11")
      (libsource (lib "OnatLib") (part "CPG151101S11 - Kailh Hotswap Socket"))
    )
    (comp (ref "SW21")
      (value "CPG151101S11")
      (footprint "CPG151101S11")
      (libsource (lib "OnatLib") (part "CPG151101S11 - Kailh Hotswap Socket"))
    )
    (comp (ref "SW22")
      (value "CPG151101S11")
      (footprint "CPG151101S11")
      (libsource (lib "OnatLib") (part "CPG151101S11 - Kailh Hotswap Socket"))
    )
    (comp (ref "SW23")
      (value "CPG151101S11")
      (footprint "CPG151101S11")
      (libsource (lib "OnatLib") (part "CPG151101S11 - Kailh Hotswap Socket"))
    )
    (comp (ref "SW24")
      (value "CPG151101S11")
      (footprint "CPG151101S11")
      (libsource (lib "OnatLib") (part "CPG151101S11 - Kailh Hotswap Socket"))
    )
    (comp (ref "SW25")
      (value "CPG151101S11")
      (footprint "CPG151101S11")
      (libsource (lib "OnatLib") (part "CPG151101S11 - Kailh Hotswap Socket"))
    )
    (comp (ref "SW26")
      (value "CPG151101S11")
      (footprint "CPG151101S11")
      (libsource (lib "OnatLib") (part "CPG151101S11 - Kailh Hotswap Socket"))
    )
    (comp (ref "SW27")
      (value "CPG151101S11")
      (footprint "CPG151101S11")
      (libsource (lib "OnatLib") (part "CPG151101S11 - Kailh Hotswap Socket"))
    )
    (comp (ref "SW28")
      (value "CPG151101S11")
      (footprint "CPG151101S11")
      (libsource (lib "OnatLib") (part "CPG151101S11 - Kailh Hotswap Socket"))
    )
    (comp (ref "SW29")
      (value "CPG151101S11")
      (footprint "CPG151101S11")
      (libsource (lib "OnatLib") (part "CPG151101S11 - Kailh Hotswap Socket"))
    )
    (comp (ref "SW30")
      (value "CPG151101S11")
      (footprint "CPG151101S11")
      (libsource (lib "OnatLib") (part "CPG151101S11 - Kailh Hotswap Socket"))
    )
    (comp (ref "SW31")
      (value "CPG151101S11")
      (footprint "CPG151101S11")
      (libsource (lib "OnatLib") (part "CPG151101S11 - Kailh Hotswap Socket"))
    )
    (comp (ref "SW32")
      (value "CPG151101S11")
      (footprint "CPG151101S11")
      (libsource (lib "OnatLib") (part "CPG151101S11 - Kailh Hotswap Socket"))
    )
    (comp (ref "SW33")
      (value "CPG151101S11")
      (footprint "CPG151101S11")
      (libsource (lib "OnatLib") (part "CPG151101S11 - Kailh Hotswap Socket"))
    )
    (comp (ref "SW34")
      (value "CPG151101S11")
      (footprint "CPG151101S11")
      (libsource (lib "OnatLib") (part "CPG151101S11 - Kailh Hotswap Socket"))
    )
    (comp (ref "SW35")
      (value "CPG151101S11")
      (footprint "CPG151101S11")
      (libsource (lib "OnatLib") (part "CPG151101S11 - Kailh Hotswap Socket"))
    )
    (comp (ref "SW36")
      (value "CPG151101S11")
      (footprint "CPG151101S11")
      (libsource (lib "OnatLib") (part "CPG151101S11 - Kailh Hotswap Socket"))
    )
    (comp (ref "SW37")
      (value "CPG151101S11")
      (footprint "CPG151101S11")
      (libsource (lib "OnatLib") (part "CPG151101S11 - Kailh Hotswap Socket"))
    )
    (comp (ref "SW38")
      (value "CPG151101S11")
      (footprint "CPG151101S11")
      (libsource (lib "OnatLib") (part "CPG151101S11 - Kailh Hotswap Socket"))
    )
    (comp (ref "SW39")
      (value "CPG151101S11")
      (footprint "CPG151101S11")
      (libsource (lib "OnatLib") (part "CPG151101S11 - Kailh Hotswap Socket"))
    )
    (comp (ref "SW40")
      (value "CPG151101S11")
      (footprint "CPG151101S11")
      (libsource (lib "OnatLib") (part "CPG151101S11 - Kailh Hotswap Socket"))
    )
    (comp (ref "SW41")
      (value "CPG151101S11")
      (footprint "CPG151101S11")
      (libsource (lib "OnatLib") (part "CPG151101S11 - Kailh Hotswap Socket"))
    )
    (comp (ref "SW42")
      (value "CPG151101S11")
      (footprint "CPG151101S11")
      (libsource (lib "OnatLib") (part "CPG151101S11 - Kailh Hotswap Socket"))
    )
    (comp (ref "SW43")
      (value "CPG151101S11")
      (footprint "CPG151101S11")
      (libsource (lib "OnatLib") (part "CPG151101S11 - Kailh Hotswap Socket"))
    )
    (comp (ref "SW44")
      (value "CPG151101S11")
      (footprint "CPG151101S11")
      (libsource (lib "OnatLib") (part "CPG151101S11 - Kailh Hotswap Socket"))
    )
    (comp (ref "SW45")
      (value "CPG151101S11")
      (footprint "CPG151101S11")
      (libsource (lib "OnatLib") (part "CPG151101S11 - Kailh Hotswap Socket"))
    )
    (comp (ref "SW46")
      (value "CPG151101S11")
      (footprint "CPG151101S11")
      (libsource (lib "OnatLib") (part "CPG151101S11 - Kailh Hotswap Socket"))
    )
    (comp (ref "SW47")
      (value "CPG151101S11")
      (footprint "CPG151101S11")
      (libsource (lib "OnatLib") (part "CPG151101S11 - Kailh Hotswap Socket"))
    )
    (comp (ref "SW48")
      (value "CPG151101S11")
      (footprint "CPG151101S11")
      (libsource (lib "OnatLib") (part "CPG151101S11 - Kailh Hotswap Socket"))
    )
    (comp (ref "SW49")
      (value "CPG151101S11")
      (footprint "CPG151101S11")
      (libsource (lib "OnatLib") (part "CPG151101S11 - Kailh Hotswap Socket"))
    )
    (comp (ref "SW50")
      (value "CPG151101S11")
      (footprint "CPG151101S11")
      (libsource (lib "OnatLib") (part "CPG151101S11 - Kailh Hotswap Socket"))
    )
    (comp (ref "SW51")
      (value "CPG151101S11")
      (footprint "CPG151101S11")
      (libsource (lib "OnatLib") (part "CPG151101S11 - Kailh Hotswap Socket"))
    )
    (comp (ref "SW52")
      (value "CPG151101S11")
      (footprint "CPG151101S11")
      (libsource (lib "OnatLib") (part "CPG151101S11 - Kailh Hotswap Socket"))
    )
    (comp (ref "SW53")
      (value "CPG151101S11")
      (footprint "CPG151101S11")
      (libsource (lib "OnatLib") (part "CPG151101S11 - Kailh Hotswap Socket"))
    )
    (comp (ref "SW54")
      (value "CPG151101S11")
      (footprint "CPG151101S11")
      (libsource (lib "OnatLib") (part "CPG151101S11 - Kailh Hotswap Socket"))
    )
    (comp (ref "SW55")
      (value "CPG151101S11")
      (footprint "CPG151101S11")
      (libsource (lib "OnatLib") (part "CPG151101S11 - Kailh Hotswap Socket"))
    )
    (comp (ref "SW56")
      (value "CPG151101S11")
      (footprint "CPG151101S11")
      (libsource (lib "OnatLib") (part "CPG151101S11 - Kailh Hotswap Socket"))
    )
    (comp (ref "SW57")
      (value "CPG151101S11")
      (footprint "CPG151101S11")
      (libsource (lib "OnatLib") (part "CPG151101S11 - Kailh Hotswap Socket"))
    )
    (comp (ref "SW58")
      (value "CPG151101S11")
      (footprint "CPG151101S11")
      (libsource (lib "OnatLib") (part "CPG151101S11 - Kailh Hotswap Socket"))
    )
    (comp (ref "SW59")
      (value "CPG151101S11")
      (footprint "CPG151101S11")
      (libsource (lib "OnatLib") (part "CPG151101S11 - Kailh Hotswap Socket"))
    )
    (comp (ref "SW60")
      (value "CPG151101S11")
      (footprint "CPG151101S11")
      (libsource (lib "OnatLib") (part "CPG151101S11 - Kailh Hotswap Socket"))
    )
    (comp (ref "SW61")
      (value "CPG151101S11")
      (footprint "CPG151101S11")
      (libsource (lib "OnatLib") (part "CPG151101S11 - Kailh Hotswap Socket"))
    )
    (comp (ref "SW62")
      (value "CPG151101S11")
      (footprint "CPG151101S11")
      (libsource (lib "OnatLib") (part "CPG151101S11 - Kailh Hotswap Socket"))
    )
    (comp (ref "SW63")
      (value "CPG151101S11")
      (footprint "CPG151101S11")
      (libsource (lib "OnatLib") (part "CPG151101S11 - Kailh Hotswap Socket"))
    )
    (comp (ref "SW64")
      (value "CPG151101S11")
      (footprint "CPG151101S11")
      (libsource (lib "OnatLib") (part "CPG151101S11 - Kailh Hotswap Socket"))
    )
    (comp (ref "SW65")
      (value "CPG151101S11")
      (footprint "CPG151101S11")
      (libsource (lib "OnatLib") (part "CPG151101S11 - Kailh Hotswap Socket"))
    )
    (comp (ref "SW66")
      (value "CPG151101S11")
      (footprint "CPG151101S11")
      (libsource (lib "OnatLib") (part "CPG151101S11 - Kailh Hotswap Socket"))
    )
    (comp (ref "SW67")
      (value "CPG151101S11")
      (footprint "CPG151101S11")
      (libsource (lib "OnatLib") (part "CPG151101S11 - Kailh Hotswap Socket"))
    )
    (comp (ref "SW68")
      (value "CPG151101S11")
      (footprint "CPG151101S11")
      (libsource (lib "OnatLib") (part "CPG151101S11 - Kailh Hotswap Socket"))
    )
    (comp (ref "SW69")
      (value "CPG151101S11")
      (footprint "CPG151101S11")
      (libsource (lib "OnatLib") (part "CPG151101S11 - Kailh Hotswap Socket"))
    )
    (comp (ref "SW70")
      (value "CPG151101S11")
      (footprint "CPG151101S11")
      (libsource (lib "OnatLib") (part "CPG151101S11 - Kailh Hotswap Socket"))
    )
    (comp (ref "SW71")
      (value "CPG151101S11")
      (footprint "CPG151101S11")
      (libsource (lib "OnatLib") (part "CPG151101S11 - Kailh Hotswap Socket"))
    )
    (comp (ref "SW72")
      (value "CPG151101S11")
      (footprint "CPG151101S11")
      (libsource (lib "OnatLib") (part "CPG151101S11 - Kailh Hotswap Socket"))
    )
    (comp (ref "SW73")
      (value "CPG151101S11")
      (footprint "CPG151101S11")
      (libsource (lib "OnatLib") (part "CPG151101S11 - Kailh Hotswap Socket"))
    )
    (comp (ref "SW74")
      (value "CPG151101S11")
      (footprint "CPG151101S11")
      (libsource (lib "OnatLib") (part "CPG151101S11 - Kailh Hotswap Socket"))
    )
    (comp (ref "SW75")
      (value "CPG151101S11")
      (footprint "CPG151101S11")
      (libsource (lib "OnatLib") (part "CPG151101S11 - Kailh Hotswap Socket"))
    )
    (comp (ref "SW76")
      (value "CPG151101S11")
      (footprint "CPG151101S11")
      (libsource (lib "OnatLib") (part "CPG151101S11 - Kailh Hotswap Socket"))
    )
    (comp (ref "SW77")
      (value "CPG151101S11")
      (footprint "CPG151101S11")
      (libsource (lib "OnatLib") (part "CPG151101S11 - Kailh Hotswap Socket"))
    )
    (comp (ref "SW78")
      (value "CPG151101S11")
      (footprint "CPG151101S11")
      (libsource (lib "OnatLib") (part "CPG151101S11 - Kailh Hotswap Socket"))
    )
    (comp (ref "U1")
      (value "USB4110-GF-A")
      (footprint "SamacSys:USB4110GFA")
      (description "Connector")
      (fields (field (name "MOUSER PART NUMBER") "640-USB4110-GF-A"))
      (libsource (lib "*") (part "USB4110-GF-A"))
    )
    (comp (ref "U2")
      (value "NCP1117ST33T3G")
      (footprint "ON SEMI SOT-223 ST(318H)")
      (description "IC REG LINEAR 3.3V 1A SOT223")
      (fields (field (name "MANUFACTURER") "ON Semiconductor"))
      (libsource (lib "Celestial Altium Library") (part "ON Semi NCP1117"))
    )
    (comp (ref "U3")
      (value "RP2040")
      (footprint "RP2040_QFN56")
      (description "Raspberry Pi RP2040 Mcu, 32 Bit, 133MHZ, QFN-56;")
      (libsource (lib "OnatLib") (part "RP2040"))
    )
    (comp (ref "U4")
      (value "USBLC6-2SC6")
      (footprint "SamacSys:SOT95P280X145-6N")
      (description "Integrated Circuit")
      (fields (field (name "MOUSER PART NUMBER") "511-USBLC6-2SC6"))
      (libsource (lib "*") (part "USBLC6-2SC6"))
    )
    (comp (ref "U5")
      (value "W25Q128JVSIQ_TR")
      (footprint "SamacSys:SOIC127P780X195-8N")
      (description "Inductor")
      (fields
        (field (name "MANUFACTURER_PART_NUMBER") "W25Q128JVSIQ TR")
        (field (name "MOUSER PART NUMBER") "454-W25Q128JVSIQTR")
      )
      (libsource (lib "*") (part "W25Q128JVSIQ_TR"))
    )
    (comp (ref "Y1")
      (value "12MHz")
      (footprint "ABRACON ABM8G")
      (description "CRYSTAL 12.0000MHZ 18PF SMD")
      (fields
        (field (name "PART NUMBER") "ABM8G-12.000MHZ-18-D2Y-T")
        (field (name "MANUFACTURER") "Abracon LLC")
      )
      (libsource (lib "Celestial Altium Library") (part "Abracon Crystal ABM8G"))
    )
  )
  (nets
    (net (code "1") (name "+1V1") (class "Default")
      (node (ref "C12") (pin "2") (pinfunction "2_2") (pintype "passive"))
      (node (ref "C3") (pin "2") (pinfunction "2_2") (pintype "passive"))
      (node (ref "C4") (pin "2") (pinfunction "2_2") (pintype "passive"))
      (node (ref "U3") (pin "23") (pinfunction "DVDD_23") (pintype "power_in"))
      (node (ref "U3") (pin "45") (pinfunction "VREG_VOUT_45") (pintype "power_in"))
      (node (ref "U3") (pin "50") (pinfunction "DVDD_50") (pintype "power_in"))
    )
    (net (code "2") (name "+3V3") (class "Default")
      (node (ref "C10") (pin "2") (pinfunction "2_2") (pintype "passive"))
      (node (ref "C11") (pin "2") (pinfunction "2_2") (pintype "passive"))
      (node (ref "C13") (pin "2") (pinfunction "2_2") (pintype "passive"))
      (node (ref "C17") (pin "2") (pinfunction "2_2") (pintype "passive"))
      (node (ref "C2") (pin "2") (pinfunction "2_2") (pintype "passive"))
      (node (ref "C5") (pin "2") (pinfunction "2_2") (pintype "passive"))
      (node (ref "C6") (pin "2") (pinfunction "2_2") (pintype "passive"))
      (node (ref "C7") (pin "2") (pinfunction "2_2") (pintype "passive"))
      (node (ref "C8") (pin "2") (pinfunction "2_2") (pintype "passive"))
      (node (ref "C9") (pin "2") (pinfunction "2_2") (pintype "passive"))
      (node (ref "R6") (pin "1") (pinfunction "1_1") (pintype "passive"))
      (node (ref "R7") (pin "1") (pinfunction "1_1") (pintype "passive"))
      (node (ref "R8") (pin "1") (pinfunction "1_1") (pintype "passive"))
      (node (ref "R9") (pin "1") (pinfunction "1_1") (pintype "passive"))
      (node (ref "U2") (pin "2") (pinfunction "VOUT_2") (pintype "passive"))
      (node (ref "U2") (pin "4") (pinfunction "VOUT_4") (pintype "passive"))
      (node (ref "U3") (pin "1") (pinfunction "IOVDD_1") (pintype "power_in"))
      (node (ref "U3") (pin "10") (pinfunction "IOVDD_10") (pintype "power_in"))
      (node (ref "U3") (pin "22") (pinfunction "IOVDD_22") (pintype "power_in"))
      (node (ref "U3") (pin "33") (pinfunction "IOVDD_33") (pintype "power_in"))
      (node (ref "U3") (pin "42") (pinfunction "IOVDD_42") (pintype "power_in"))
      (node (ref "U3") (pin "43") (pinfunction "ADC_IOVDD_43") (pintype "power_in"))
      (node (ref "U3") (pin "44") (pinfunction "VREG_IOVDD_44") (pintype "power_in"))
      (node (ref "U3") (pin "48") (pinfunction "USB_IOVDD_48") (pintype "power_in"))
      (node (ref "U3") (pin "49") (pinfunction "IOVDD_49") (pintype "power_in"))
      (node (ref "U5") (pin "8") (pinfunction "VCC_8") (pintype "passive"))
    )
    (net (code "3") (name "+5V") (class "Default")
      (node (ref "C1") (pin "2") (pinfunction "2_2") (pintype "passive"))
      (node (ref "F1") (pin "2") (pinfunction "2_2") (pintype "passive"))
      (node (ref "U2") (pin "3") (pinfunction "VIN_3") (pintype "passive"))
    )
    (net (code "4") (name "/Col1") (class "Default")
      (node (ref "D1") (pin "2") (pinfunction "K_2") (pintype "passive"))
      (node (ref "D17") (pin "2") (pinfunction "K_2") (pintype "passive"))
      (node (ref "D34") (pin "2") (pinfunction "K_2") (pintype "passive"))
      (node (ref "D50") (pin "2") (pinfunction "K_2") (pintype "passive"))
      (node (ref "D66") (pin "2") (pinfunction "K_2") (pintype "passive"))
      (node (ref "U3") (pin "34") (pinfunction "GPIO22_34") (pintype "bidirectional"))
    )
    (net (code "5") (name "/Col2") (class "Default")
      (node (ref "D18") (pin "2") (pinfunction "K_2") (pintype "passive"))
      (node (ref "D2") (pin "2") (pinfunction "K_2") (pintype "passive"))
      (node (ref "D35") (pin "2") (pinfunction "K_2") (pintype "passive"))
      (node (ref "D51") (pin "2") (pinfunction "K_2") (pintype "passive"))
      (node (ref "D67") (pin "2") (pinfunction "K_2") (pintype "passive"))
      (node (ref "U3") (pin "35") (pinfunction "GPIO23_35") (pintype "bidirectional"))
    )
    (net (code "6") (name "/Col3") (class "Default")
      (node (ref "D19") (pin "2") (pinfunction "K_2") (pintype "passive"))
      (node (ref "D3") (pin "2") (pinfunction "K_2") (pintype "passive"))
      (node (ref "D36") (pin "2") (pinfunction "K_2") (pintype "passive"))
      (node (ref "D52") (pin "2") (pinfunction "K_2") (pintype "passive"))
      (node (ref "D68") (pin "2") (pinfunction "K_2") (pintype "passive"))
      (node (ref "U3") (pin "36") (pinfunction "GPIO24_36") (pintype "bidirectional"))
    )
    (net (code "7") (name "/Col4") (class "Default")
      (node (ref "D20") (pin "2") (pinfunction "K_2") (pintype "passive"))
      (node (ref "D37") (pin "2") (pinfunction "K_2") (pintype "passive"))
      (node (ref "D4") (pin "2") (pinfunction "K_2") (pintype "passive"))
      (node (ref "D53") (pin "2") (pinfunction "K_2") (pintype "passive"))
      (node (ref "D69") (pin "2") (pinfunction "K_2") (pintype "passive"))
      (node (ref "U3") (pin "37") (pinfunction "GPIO25_37") (pintype "bidirectional"))
    )
    (net (code "8") (name "/Col5") (class "Default")
      (node (ref "D21") (pin "2") (pinfunction "K_2") (pintype "passive"))
      (node (ref "D38") (pin "2") (pinfunction "K_2") (pintype "passive"))
      (node (ref "D5") (pin "2") (pinfunction "K_2") (pintype "passive"))
      (node (ref "D54") (pin "2") (pinfunction "K_2") (pintype "passive"))
      (node (ref "U3") (pin "5") (pinfunction "GPIO3_5") (pintype "bidirectional"))
    )
    (net (code "9") (name "/Col6") (class "Default")
      (node (ref "D22") (pin "2") (pinfunction "K_2") (pintype "passive"))
      (node (ref "D39") (pin "2") (pinfunction "K_2") (pintype "passive"))
      (node (ref "D55") (pin "2") (pinfunction "K_2") (pintype "passive"))
      (node (ref "D6") (pin "2") (pinfunction "K_2") (pintype "passive"))
      (node (ref "U3") (pin "4") (pinfunction "GPIO2_4") (pintype "bidirectional"))
    )
    (net (code "10") (name "/Col7") (class "Default")
      (node (ref "D23") (pin "2") (pinfunction "K_2") (pintype "passive"))
      (node (ref "D40") (pin "2") (pinfunction "K_2") (pintype "passive"))
      (node (ref "D56") (pin "2") (pinfunction "K_2") (pintype "passive"))
      (node (ref "D7") (pin "2") (pinfunction "K_2") (pintype "passive"))
      (node (ref "D70") (pin "2") (pinfunction "K_2") (pintype "passive"))
      (node (ref "U3") (pin "3") (pinfunction "GPIO1_3") (pintype "bidirectional"))
    )
    (net (code "11") (name "/Col8") (class "Default")
      (node (ref "D24") (pin "2") (pinfunction "K_2") (pintype "passive"))
      (node (ref "D41") (pin "2") (pinfunction "K_2") (pintype "passive"))
      (node (ref "D57") (pin "2") (pinfunction "K_2") (pintype "passive"))
      (node (ref "D71") (pin "2") (pinfunction "K_2") (pintype "passive"))
      (node (ref "D8") (pin "2") (pinfunction "K_2") (pintype "passive"))
      (node (ref "U3") (pin "2") (pinfunction "GPIO0_2") (pintype "bidirectional"))
    )
    (net (code "12") (name "/Col9") (class "Default")
      (node (ref "D25") (pin "2") (pinfunction "K_2") (pintype "passive"))
      (node (ref "D42") (pin "2") (pinfunction "K_2") (pintype "passive"))
      (node (ref "D58") (pin "2") (pinfunction "K_2") (pintype "passive"))
      (node (ref "D72") (pin "2") (pinfunction "K_2") (pintype "passive"))
      (node (ref "D9") (pin "2") (pinfunction "K_2") (pintype "passive"))
      (node (ref "U3") (pin "32") (pinfunction "GPIO21_32") (pintype "bidirectional"))
    )
    (net (code "13") (name "/Col10") (class "Default")
      (node (ref "D10") (pin "2") (pinfunction "K_2") (pintype "passive"))
      (node (ref "D26") (pin "2") (pinfunction "K_2") (pintype "passive"))
      (node (ref "D43") (pin "2") (pinfunction "K_2") (pintype "passive"))
      (node (ref "D59") (pin "2") (pinfunction "K_2") (pintype "passive"))
      (node (ref "D73") (pin "2") (pinfunction "K_2") (pintype "passive"))
      (node (ref "U3") (pin "29") (pinfunction "GPIO18_29") (pintype "bidirectional"))
    )
    (net (code "14") (name "/Col11") (class "Default")
      (node (ref "D11") (pin "2") (pinfunction "K_2") (pintype "passive"))
      (node (ref "D27") (pin "2") (pinfunction "K_2") (pintype "passive"))
      (node (ref "D44") (pin "2") (pinfunction "K_2") (pintype "passive"))
      (node (ref "U3") (pin "28") (pinfunction "GPIO17_28") (pintype "bidirectional"))
      (node (ref "U3") (pin "30") (pinfunction "GPIO19_30") (pintype "bidirectional"))
    )
    (net (code "15") (name "/Col12") (class "Default")
      (node (ref "D12") (pin "2") (pinfunction "K_2") (pintype "passive"))
      (node (ref "D28") (pin "2") (pinfunction "K_2") (pintype "passive"))
      (node (ref "D45") (pin "2") (pinfunction "K_2") (pintype "passive"))
      (node (ref "D60") (pin "2") (pinfunction "K_2") (pintype "passive"))
      (node (ref "D74") (pin "2") (pinfunction "K_2") (pintype "passive"))
      (node (ref "U3") (pin "27") (pinfunction "GPIO16_27") (pintype "bidirectional"))
      (node (ref "U3") (pin "31") (pinfunction "GPIO20_31") (pintype "bidirectional"))
    )
    (net (code "16") (name "/Col13") (class "Default")
      (node (ref "D13") (pin "2") (pinfunction "K_2") (pintype "passive"))
      (node (ref "D29") (pin "2") (pinfunction "K_2") (pintype "passive"))
      (node (ref "D46") (pin "2") (pinfunction "K_2") (pintype "passive"))
      (node (ref "D61") (pin "2") (pinfunction "K_2") (pintype "passive"))
      (node (ref "D75") (pin "2") (pinfunction "K_2") (pintype "passive"))
      (node (ref "U3") (pin "18") (pinfunction "GPIO15_18") (pintype "bidirectional"))
    )
    (net (code "17") (name "/Col14") (class "Default")
      (node (ref "D30") (pin "2") (pinfunction "K_2") (pintype "passive"))
      (node (ref "D62") (pin "2") (pinfunction "K_2") (pintype "passive"))
      (node (ref "D76") (pin "2") (pinfunction "K_2") (pintype "passive"))
      (node (ref "U3") (pin "17") (pinfunction "GPIO14_17") (pintype "bidirectional"))
    )
    (net (code "18") (name "/Col15") (class "Default")
      (node (ref "D14") (pin "2") (pinfunction "K_2") (pintype "passive"))
      (node (ref "D31") (pin "2") (pinfunction "K_2") (pintype "passive"))
      (node (ref "D47") (pin "2") (pinfunction "K_2") (pintype "passive"))
      (node (ref "D63") (pin "2") (pinfunction "K_2") (pintype "passive"))
      (node (ref "D77") (pin "2") (pinfunction "K_2") (pintype "passive"))
      (node (ref "U3") (pin "13") (pinfunction "GPIO10_13") (pintype "bidirectional"))
    )
    (net (code "19") (name "/Col16") (class "Default")
      (node (ref "D15") (pin "2") (pinfunction "K_2") (pintype "passive"))
      (node (ref "D32") (pin "2") (pinfunction "K_2") (pintype "passive"))
      (node (ref "D48") (pin "2") (pinfunction "K_2") (pintype "passive"))
      (node (ref "D64") (pin "2") (pinfunction "K_2") (pintype "passive"))
      (node (ref "U3") (pin "12") (pinfunction "GPIO9_12") (pintype "bidirectional"))
    )
    (net (code "20") (name "/Col17") (class "Default")
      (node (ref "D16") (pin "2") (pinfunction "K_2") (pintype "passive"))
      (node (ref "D33") (pin "2") (pinfunction "K_2") (pintype "passive"))
      (node (ref "D49") (pin "2") (pinfunction "K_2") (pintype "passive"))
      (node (ref "D65") (pin "2") (pinfunction "K_2") (pintype "passive"))
      (node (ref "D78") (pin "2") (pinfunction "K_2") (pintype "passive"))
      (node (ref "U3") (pin "11") (pinfunction "GPIO8_11") (pintype "bidirectional"))
    )
    (net (code "21") (name "/ENCA") (class "Default")
      (node (ref "C18") (pin "2") (pinfunction "2_2") (pintype "passive"))
      (node (ref "R11") (pin "2") (pinfunction "2_2") (pintype "passive"))
      (node (ref "U3") (pin "15") (pinfunction "GPIO12_15") (pintype "bidirectional"))
    )
    (net (code "22") (name "/ENCB") (class "Default")
      (node (ref "C19") (pin "2") (pinfunction "2_2") (pintype "passive"))
      (node (ref "R12") (pin "2") (pinfunction "2_2") (pintype "passive"))
      (node (ref "U3") (pin "16") (pinfunction "GPIO13_16") (pintype "bidirectional"))
    )
    (net (code "23") (name "/ENCSW") (class "Default")
      (node (ref "ENC1") (pin "2") (pinfunction "2_2") (pintype "passive"))
      (node (ref "R7") (pin "2") (pinfunction "2_2") (pintype "passive"))
      (node (ref "U3") (pin "14") (pinfunction "GPIO11_14") (pintype "bidirectional"))
    )
    (net (code "24") (name "/QSPI_SCLK") (class "Default")
      (node (ref "U3") (pin "52") (pinfunction "QSPI_SCLK_52") (pintype "bidirectional"))
      (node (ref "U5") (pin "6") (pinfunction "CLK_6") (pintype "passive"))
    )
    (net (code "25") (name "/QSPI_SD0") (class "Default")
      (node (ref "U3") (pin "53") (pinfunction "QSPI_SD0_53") (pintype "bidirectional"))
      (node (ref "U5") (pin "5") (pinfunction "DI_(IO0)_5") (pintype "passive"))
    )
    (net (code "26") (name "/QSPI_SD1") (class "Default")
      (node (ref "U3") (pin "55") (pinfunction "QSPI_SD1_55") (pintype "bidirectional"))
      (node (ref "U5") (pin "2") (pinfunction "DO_(IO1)_2") (pintype "passive"))
    )
    (net (code "27") (name "/QSPI_SD2") (class "Default")
      (node (ref "U3") (pin "54") (pinfunction "QSPI_SD2_54") (pintype "bidirectional"))
      (node (ref "U5") (pin "3") (pinfunction "IO2_3") (pintype "passive"))
    )
    (net (code "28") (name "/QSPI_SD3") (class "Default")
      (node (ref "U3") (pin "51") (pinfunction "QSPI_SD3_51") (pintype "bidirectional"))
      (node (ref "U5") (pin "7") (pinfunction "IO_7") (pintype "passive"))
    )
    (net (code "29") (name "/QSPI_SS") (class "Default")
      (node (ref "R14") (pin "2") (pinfunction "2_2") (pintype "passive"))
      (node (ref "U3") (pin "56") (pinfunction "QSPI_SS_56") (pintype "bidirectional"))
      (node (ref "U5") (pin "1") (pinfunction "/CS_1") (pintype "passive"))
    )
    (net (code "30") (name "/RUN") (class "Default")
      (node (ref "R10") (pin "2") (pinfunction "2_2") (pintype "passive"))
      (node (ref "R6") (pin "2") (pinfunction "2_2") (pintype "passive"))
      (node (ref "U3") (pin "26") (pinfunction "RUN_26") (pintype "input"))
    )
    (net (code "31") (name "/Row1") (class "Default")
      (node (ref "SW1") (pin "1") (pinfunction "1_1") (pintype "passive"))
      (node (ref "SW10") (pin "1") (pinfunction "1_1") (pintype "passive"))
      (node (ref "SW11") (pin "1") (pinfunction "1_1") (pintype "passive"))
      (node (ref "SW12") (pin "1") (pinfunction "1_1") (pintype "passive"))
      (node (ref "SW13") (pin "1") (pinfunction "1_1") (pintype "passive"))
      (node (ref "SW14") (pin "1") (pinfunction "1_1") (pintype "passive"))
      (node (ref "SW15") (pin "1") (pinfunction "1_1") (pintype "passive"))
      (node (ref "SW16") (pin "1") (pinfunction "1_1") (pintype "passive"))
      (node (ref "SW2") (pin "1") (pinfunction "1_1") (pintype "passive"))
      (node (ref "SW3") (pin "1") (pinfunction "1_1") (pintype "passive"))
      (node (ref "SW4") (pin "1") (pinfunction "1_1") (pintype "passive"))
      (node (ref "SW5") (pin "1") (pinfunction "1_1") (pintype "passive"))
      (node (ref "SW6") (pin "1") (pinfunction "1_1") (pintype "passive"))
      (node (ref "SW7") (pin "1") (pinfunction "1_1") (pintype "passive"))
      (node (ref "SW8") (pin "1") (pinfunction "1_1") (pintype "passive"))
      (node (ref "SW9") (pin "1") (pinfunction "1_1") (pintype "passive"))
      (node (ref "U3") (pin "6") (pinfunction "GPIO4_6") (pintype "bidirectional"))
    )
    (net (code "32") (name "/Row2") (class "Default")
      (node (ref "SW17") (pin "1") (pinfunction "1_1") (pintype "passive"))
      (node (ref "SW18") (pin "1") (pinfunction "1_1") (pintype "passive"))
      (node (ref "SW19") (pin "1") (pinfunction "1_1") (pintype "passive"))
      (node (ref "SW20") (pin "1") (pinfunction "1_1") (pintype "passive"))
      (node (ref "SW21") (pin "1") (pinfunction "1_1") (pintype "passive"))
      (node (ref "SW22") (pin "1") (pinfunction "1_1") (pintype "passive"))
      (node (ref "SW23") (pin "1") (pinfunction "1_1") (pintype "passive"))
      (node (ref "SW24") (pin "1") (pinfunction "1_1") (pintype "passive"))
      (node (ref "SW25") (pin "1") (pinfunction "1_1") (pintype "passive"))
      (node (ref "SW26") (pin "1") (pinfunction "1_1") (pintype "passive"))
      (node (ref "SW27") (pin "1") (pinfunction "1_1") (pintype "passive"))
      (node (ref "SW28") (pin "1") (pinfunction "1_1") (pintype "passive"))
      (node (ref "SW29") (pin "1") (pinfunction "1_1") (pintype "passive"))
      (node (ref "SW30") (pin "1") (pinfunction "1_1") (pintype "passive"))
      (node (ref "SW31") (pin "1") (pinfunction "1_1") (pintype "passive"))
      (node (ref "SW32") (pin "1") (pinfunction "1_1") (pintype "passive"))
      (node (ref "SW33") (pin "1") (pinfunction "1_1") (pintype "passive"))
      (node (ref "U3") (pin "7") (pinfunction "GPIO5_7") (pintype "bidirectional"))
    )
    (net (code "33") (name "/Row3") (class "Default")
      (node (ref "SW34") (pin "1") (pinfunction "1_1") (pintype "passive"))
      (node (ref "SW35") (pin "1") (pinfunction "1_1") (pintype "passive"))
      (node (ref "SW36") (pin "1") (pinfunction "1_1") (pintype "passive"))
      (node (ref "SW37") (pin "1") (pinfunction "1_1") (pintype "passive"))
      (node (ref "SW38") (pin "1") (pinfunction "1_1") (pintype "passive"))
      (node (ref "SW39") (pin "1") (pinfunction "1_1") (pintype "passive"))
      (node (ref "SW40") (pin "1") (pinfunction "1_1") (pintype "passive"))
      (node (ref "SW41") (pin "1") (pinfunction "1_1") (pintype "passive"))
      (node (ref "SW42") (pin "1") (pinfunction "1_1") (pintype "passive"))
      (node (ref "SW43") (pin "1") (pinfunction "1_1") (pintype "passive"))
      (node (ref "SW44") (pin "1") (pinfunction "1_1") (pintype "passive"))
      (node (ref "SW45") (pin "1") (pinfunction "1_1") (pintype "passive"))
      (node (ref "SW46") (pin "1") (pinfunction "1_1") (pintype "passive"))
      (node (ref "SW47") (pin "1") (pinfunction "1_1") (pintype "passive"))
      (node (ref "SW48") (pin "1") (pinfunction "1_1") (pintype "passive"))
      (node (ref "SW49") (pin "1") (pinfunction "1_1") (pintype "passive"))
      (node (ref "U3") (pin "8") (pinfunction "GPIO6_8") (pintype "bidirectional"))
    )
    (net (code "34") (name "/Row4") (class "Default")
      (node (ref "SW50") (pin "1") (pinfunction "1_1") (pintype "passive"))
      (node (ref "SW51") (pin "1") (pinfunction "1_1") (pintype "passive"))
      (node (ref "SW52") (pin "1") (pinfunction "1_1") (pintype "passive"))
      (node (ref "SW53") (pin "1") (pinfunction "1_1") (pintype "passive"))
      (node (ref "SW54") (pin "1") (pinfunction "1_1") (pintype "passive"))
      (node (ref "SW55") (pin "1") (pinfunction "1_1") (pintype "passive"))
      (node (ref "SW56") (pin "1") (pinfunction "1_1") (pintype "passive"))
      (node (ref "SW57") (pin "1") (pinfunction "1_1") (pintype "passive"))
      (node (ref "SW58") (pin "1") (pinfunction "1_1") (pintype "passive"))
      (node (ref "SW59") (pin "1") (pinfunction "1_1") (pintype "passive"))
      (node (ref "SW60") (pin "1") (pinfunction "1_1") (pintype "passive"))
      (node (ref "SW61") (pin "1") (pinfunction "1_1") (pintype "passive"))
      (node (ref "SW62") (pin "1") (pinfunction "1_1") (pintype "passive"))
      (node (ref "SW63") (pin "1") (pinfunction "1_1") (pintype "passive"))
      (node (ref "SW64") (pin "1") (pinfunction "1_1") (pintype "passive"))
      (node (ref "SW65") (pin "1") (pinfunction "1_1") (pintype "passive"))
      (node (ref "U3") (pin "9") (pinfunction "GPIO7_9") (pintype "bidirectional"))
    )
    (net (code "35") (name "/Row5") (class "Default")
      (node (ref "SW66") (pin "1") (pinfunction "1_1") (pintype "passive"))
      (node (ref "SW67") (pin "1") (pinfunction "1_1") (pintype "passive"))
      (node (ref "SW68") (pin "1") (pinfunction "1_1") (pintype "passive"))
      (node (ref "SW69") (pin "1") (pinfunction "1_1") (pintype "passive"))
      (node (ref "SW70") (pin "1") (pinfunction "1_1") (pintype "passive"))
      (node (ref "SW71") (pin "1") (pinfunction "1_1") (pintype "passive"))
      (node (ref "SW72") (pin "1") (pinfunction "1_1") (pintype "passive"))
      (node (ref "SW73") (pin "1") (pinfunction "1_1") (pintype "passive"))
      (node (ref "SW74") (pin "1") (pinfunction "1_1") (pintype "passive"))
      (node (ref "SW75") (pin "1") (pinfunction "1_1") (pintype "passive"))
      (node (ref "SW76") (pin "1") (pinfunction "1_1") (pintype "passive"))
      (node (ref "SW77") (pin "1") (pinfunction "1_1") (pintype "passive"))
      (node (ref "SW78") (pin "1") (pinfunction "1_1") (pintype "passive"))
    )
    (net (code "36") (name "/SWCLK") (class "Default")
      (node (ref "J1") (pin "0") (pinfunction "0_0") (pintype "passive"))
      (node (ref "U3") (pin "24") (pinfunction "SWCLK_24") (pintype "input"))
    )
    (net (code "37") (name "/SWD") (class "Default")
      (node (ref "J2") (pin "0") (pinfunction "0_0") (pintype "passive"))
      (node (ref "U3") (pin "25") (pinfunction "SWD_25") (pintype "bidirectional"))
    )
    (net (code "38") (name "/USB_BOOT") (class "Default")
      (node (ref "R13") (pin "2") (pinfunction "2_2") (pintype "passive"))
      (node (ref "R14") (pin "1") (pinfunction "1_1") (pintype "passive"))
    )
    (net (code "39") (name "/USB_N") (class "Default")
      (node (ref "U1") (pin "A7") (pinfunction "A7_A7") (pintype "passive"))
      (node (ref "U1") (pin "B7") (pinfunction "B7_B7") (pintype "passive"))
      (node (ref "U4") (pin "1") (pinfunction "I/O1_1_1") (pintype "passive"))
    )
    (net (code "40") (name "/USB_P") (class "Default")
      (node (ref "U1") (pin "A6") (pinfunction "A6_A6") (pintype "passive"))
      (node (ref "U1") (pin "B6") (pinfunction "B6_B6") (pintype "passive"))
      (node (ref "U4") (pin "3") (pinfunction "I/O2_1_3") (pintype "passive"))
    )
    (net (code "41") (name "/USB_TVS_N") (class "Default")
      (node (ref "R4") (pin "2") (pinfunction "2_2") (pintype "passive"))
      (node (ref "U4") (pin "6") (pinfunction "I/O1_2_6") (pintype "passive"))
    )
    (net (code "42") (name "/USB_TVS_P") (class "Default")
      (node (ref "R3") (pin "2") (pinfunction "2_2") (pintype "passive"))
      (node (ref "U4") (pin "4") (pinfunction "I/O2_2_4") (pintype "passive"))
    )
    (net (code "43") (name "GND") (class "Default")
      (node (ref "C1") (pin "1") (pinfunction "1_1") (pintype "passive"))
      (node (ref "C10") (pin "1") (pinfunction "1_1") (pintype "passive"))
      (node (ref "C11") (pin "1") (pinfunction "1_1") (pintype "passive"))
      (node (ref "C12") (pin "1") (pinfunction "1_1") (pintype "passive"))
      (node (ref "C13") (pin "1") (pinfunction "1_1") (pintype "passive"))
      (node (ref "C14") (pin "1") (pinfunction "1_1") (pintype "passive"))
      (node (ref "C15") (pin "1") (pinfunction "1_1") (pintype "passive"))
      (node (ref "C16") (pin "1") (pinfunction "1_1") (pintype "passive"))
      (node (ref "C17") (pin "1") (pinfunction "1_1") (pintype "passive"))
      (node (ref "C18") (pin "1") (pinfunction "1_1") (pintype "passive"))
      (node (ref "C19") (pin "1") (pinfunction "1_1") (pintype "passive"))
      (node (ref "C2") (pin "1") (pinfunction "1_1") (pintype "passive"))
      (node (ref "C3") (pin "1") (pinfunction "1_1") (pintype "passive"))
      (node (ref "C4") (pin "1") (pinfunction "1_1") (pintype "passive"))
      (node (ref "C5") (pin "1") (pinfunction "1_1") (pintype "passive"))
      (node (ref "C6") (pin "1") (pinfunction "1_1") (pintype "passive"))
      (node (ref "C7") (pin "1") (pinfunction "1_1") (pintype "passive"))
      (node (ref "C8") (pin "1") (pinfunction "1_1") (pintype "passive"))
      (node (ref "C9") (pin "1") (pinfunction "1_1") (pintype "passive"))
      (node (ref "ENC1") (pin "1") (pinfunction "1_1") (pintype "passive"))
      (node (ref "ENC1") (pin "C") (pinfunction "COMMON_C") (pintype "passive"))
      (node (ref "J3") (pin "0") (pinfunction "0_0") (pintype "passive"))
      (node (ref "R1") (pin "2") (pinfunction "2_2") (pintype "passive"))
      (node (ref "R10") (pin "1") (pinfunction "1_1") (pintype "passive"))
      (node (ref "R13") (pin "1") (pinfunction "1_1") (pintype "passive"))
      (node (ref "R2") (pin "1") (pinfunction "1_1") (pintype "passive"))
      (node (ref "U1") (pin "A1") (pinfunction "A1_A1") (pintype "passive"))
      (node (ref "U1") (pin "A12") (pinfunction "A12_A12") (pintype "passive"))
      (node (ref "U1") (pin "B1") (pinfunction "B1_B1") (pintype "passive"))
      (node (ref "U1") (pin "B12") (pinfunction "B12_B12") (pintype "passive"))
      (node (ref "U2") (pin "1") (pinfunction "GND_1") (pintype "passive"))
      (node (ref "U3") (pin "19") (pinfunction "TESTEN_19") (pintype "input"))
      (node (ref "U3") (pin "57") (pinfunction "VSS_57") (pintype "power_in"))
      (node (ref "U4") (pin "2") (pinfunction "GND_2") (pintype "passive"))
      (node (ref "U5") (pin "4") (pinfunction "GND_4") (pintype "passive"))
      (node (ref "Y1") (pin "2") (pinfunction "GND_2") (pintype "passive"))
      (node (ref "Y1") (pin "4") (pinfunction "GND_4") (pintype "passive"))
    )
    (net (code "44") (name "Net-(C16-Pad2)") (class "Default")
      (node (ref "C16") (pin "2") (pinfunction "2_2") (pintype "passive"))
      (node (ref "R5") (pin "1") (pinfunction "1_1") (pintype "passive"))
      (node (ref "Y1") (pin "3") (pinfunction "3_3") (pintype "passive"))
    )
    (net (code "45") (name "Net-(D1-A)") (class "Default")
      (node (ref "D1") (pin "1") (pinfunction "A_1") (pintype "passive"))
      (node (ref "SW1") (pin "2") (pinfunction "2_2") (pintype "passive"))
    )
    (net (code "46") (name "Net-(D2-A)") (class "Default")
      (node (ref "D2") (pin "1") (pinfunction "A_1") (pintype "passive"))
      (node (ref "SW2") (pin "2") (pinfunction "2_2") (pintype "passive"))
    )
    (net (code "47") (name "Net-(D3-A)") (class "Default")
      (node (ref "D3") (pin "1") (pinfunction "A_1") (pintype "passive"))
      (node (ref "SW3") (pin "2") (pinfunction "2_2") (pintype "passive"))
    )
    (net (code "48") (name "Net-(D4-A)") (class "Default")
      (node (ref "D4") (pin "1") (pinfunction "A_1") (pintype "passive"))
      (node (ref "SW4") (pin "2") (pinfunction "2_2") (pintype "passive"))
    )
    (net (code "49") (name "Net-(D5-A)") (class "Default")
      (node (ref "D5") (pin "1") (pinfunction "A_1") (pintype "passive"))
      (node (ref "SW5") (pin "2") (pinfunction "2_2") (pintype "passive"))
    )
    (net (code "50") (name "Net-(D6-A)") (class "Default")
      (node (ref "D6") (pin "1") (pinfunction "A_1") (pintype "passive"))
      (node (ref "SW6") (pin "2") (pinfunction "2_2") (pintype "passive"))
    )
    (net (code "51") (name "Net-(D7-A)") (class "Default")
      (node (ref "D7") (pin "1") (pinfunction "A_1") (pintype "passive"))
      (node (ref "SW7") (pin "2") (pinfunction "2_2") (pintype "passive"))
    )
    (net (code "52") (name "Net-(D8-A)") (class "Default")
      (node (ref "D8") (pin "1") (pinfunction "A_1") (pintype "passive"))
      (node (ref "SW8") (pin "2") (pinfunction "2_2") (pintype "passive"))
    )
    (net (code "53") (name "Net-(D9-A)") (class "Default")
      (node (ref "D9") (pin "1") (pinfunction "A_1") (pintype "passive"))
      (node (ref "SW9") (pin "2") (pinfunction "2_2") (pintype "passive"))
    )
    (net (code "54") (name "Net-(D10-A)") (class "Default")
      (node (ref "D10") (pin "1") (pinfunction "A_1") (pintype "passive"))
      (node (ref "SW10") (pin "2") (pinfunction "2_2") (pintype "passive"))
    )
    (net (code "55") (name "Net-(D11-A)") (class "Default")
      (node (ref "D11") (pin "1") (pinfunction "A_1") (pintype "passive"))
      (node (ref "SW11") (pin "2") (pinfunction "2_2") (pintype "passive"))
    )
    (net (code "56") (name "Net-(D12-A)") (class "Default")
      (node (ref "D12") (pin "1") (pinfunction "A_1") (pintype "passive"))
      (node (ref "SW12") (pin "2") (pinfunction "2_2") (pintype "passive"))
    )
    (net (code "57") (name "Net-(D13-A)") (class "Default")
      (node (ref "D13") (pin "1") (pinfunction "A_1") (pintype "passive"))
      (node (ref "SW13") (pin "2") (pinfunction "2_2") (pintype "passive"))
    )
    (net (code "58") (name "Net-(D14-A)") (class "Default")
      (node (ref "D14") (pin "1") (pinfunction "A_1") (pintype "passive"))
      (node (ref "SW14") (pin "2") (pinfunction "2_2") (pintype "passive"))
    )
    (net (code "59") (name "Net-(D15-A)") (class "Default")
      (node (ref "D15") (pin "1") (pinfunction "A_1") (pintype "passive"))
      (node (ref "SW15") (pin "2") (pinfunction "2_2") (pintype "passive"))
    )
    (net (code "60") (name "Net-(D16-A)") (class "Default")
      (node (ref "D16") (pin "1") (pinfunction "A_1") (pintype "passive"))
      (node (ref "SW16") (pin "2") (pinfunction "2_2") (pintype "passive"))
    )
    (net (code "61") (name "Net-(D17-A)") (class "Default")
      (node (ref "D17") (pin "1") (pinfunction "A_1") (pintype "passive"))
      (node (ref "SW17") (pin "2") (pinfunction "2_2") (pintype "passive"))
    )
    (net (code "62") (name "Net-(D18-A)") (class "Default")
      (node (ref "D18") (pin "1") (pinfunction "A_1") (pintype "passive"))
      (node (ref "SW18") (pin "2") (pinfunction "2_2") (pintype "passive"))
    )
    (net (code "63") (name "Net-(D19-A)") (class "Default")
      (node (ref "D19") (pin "1") (pinfunction "A_1") (pintype "passive"))
      (node (ref "SW19") (pin "2") (pinfunction "2_2") (pintype "passive"))
    )
    (net (code "64") (name "Net-(D20-A)") (class "Default")
      (node (ref "D20") (pin "1") (pinfunction "A_1") (pintype "passive"))
      (node (ref "SW20") (pin "2") (pinfunction "2_2") (pintype "passive"))
    )
    (net (code "65") (name "Net-(D21-A)") (class "Default")
      (node (ref "D21") (pin "1") (pinfunction "A_1") (pintype "passive"))
      (node (ref "SW21") (pin "2") (pinfunction "2_2") (pintype "passive"))
    )
    (net (code "66") (name "Net-(D22-A)") (class "Default")
      (node (ref "D22") (pin "1") (pinfunction "A_1") (pintype "passive"))
      (node (ref "SW22") (pin "2") (pinfunction "2_2") (pintype "passive"))
    )
    (net (code "67") (name "Net-(D23-A)") (class "Default")
      (node (ref "D23") (pin "1") (pinfunction "A_1") (pintype "passive"))
      (node (ref "SW23") (pin "2") (pinfunction "2_2") (pintype "passive"))
    )
    (net (code "68") (name "Net-(D24-A)") (class "Default")
      (node (ref "D24") (pin "1") (pinfunction "A_1") (pintype "passive"))
      (node (ref "SW24") (pin "2") (pinfunction "2_2") (pintype "passive"))
    )
    (net (code "69") (name "Net-(D25-A)") (class "Default")
      (node (ref "D25") (pin "1") (pinfunction "A_1") (pintype "passive"))
      (node (ref "SW25") (pin "2") (pinfunction "2_2") (pintype "passive"))
    )
    (net (code "70") (name "Net-(D26-A)") (class "Default")
      (node (ref "D26") (pin "1") (pinfunction "A_1") (pintype "passive"))
      (node (ref "SW26") (pin "2") (pinfunction "2_2") (pintype "passive"))
    )
    (net (code "71") (name "Net-(D27-A)") (class "Default")
      (node (ref "D27") (pin "1") (pinfunction "A_1") (pintype "passive"))
      (node (ref "SW27") (pin "2") (pinfunction "2_2") (pintype "passive"))
    )
    (net (code "72") (name "Net-(D28-A)") (class "Default")
      (node (ref "D28") (pin "1") (pinfunction "A_1") (pintype "passive"))
      (node (ref "SW28") (pin "2") (pinfunction "2_2") (pintype "passive"))
    )
    (net (code "73") (name "Net-(D29-A)") (class "Default")
      (node (ref "D29") (pin "1") (pinfunction "A_1") (pintype "passive"))
      (node (ref "SW29") (pin "2") (pinfunction "2_2") (pintype "passive"))
    )
    (net (code "74") (name "Net-(D30-A)") (class "Default")
      (node (ref "D30") (pin "1") (pinfunction "A_1") (pintype "passive"))
      (node (ref "SW30") (pin "2") (pinfunction "2_2") (pintype "passive"))
    )
    (net (code "75") (name "Net-(D31-A)") (class "Default")
      (node (ref "D31") (pin "1") (pinfunction "A_1") (pintype "passive"))
      (node (ref "SW31") (pin "2") (pinfunction "2_2") (pintype "passive"))
    )
    (net (code "76") (name "Net-(D32-A)") (class "Default")
      (node (ref "D32") (pin "1") (pinfunction "A_1") (pintype "passive"))
      (node (ref "SW32") (pin "2") (pinfunction "2_2") (pintype "passive"))
    )
    (net (code "77") (name "Net-(D33-A)") (class "Default")
      (node (ref "D33") (pin "1") (pinfunction "A_1") (pintype "passive"))
      (node (ref "SW33") (pin "2") (pinfunction "2_2") (pintype "passive"))
    )
    (net (code "78") (name "Net-(D34-A)") (class "Default")
      (node (ref "D34") (pin "1") (pinfunction "A_1") (pintype "passive"))
      (node (ref "SW34") (pin "2") (pinfunction "2_2") (pintype "passive"))
    )
    (net (code "79") (name "Net-(D35-A)") (class "Default")
      (node (ref "D35") (pin "1") (pinfunction "A_1") (pintype "passive"))
      (node (ref "SW35") (pin "2") (pinfunction "2_2") (pintype "passive"))
    )
    (net (code "80") (name "Net-(D36-A)") (class "Default")
      (node (ref "D36") (pin "1") (pinfunction "A_1") (pintype "passive"))
      (node (ref "SW36") (pin "2") (pinfunction "2_2") (pintype "passive"))
    )
    (net (code "81") (name "Net-(D37-A)") (class "Default")
      (node (ref "D37") (pin "1") (pinfunction "A_1") (pintype "passive"))
      (node (ref "SW37") (pin "2") (pinfunction "2_2") (pintype "passive"))
    )
    (net (code "82") (name "Net-(D38-A)") (class "Default")
      (node (ref "D38") (pin "1") (pinfunction "A_1") (pintype "passive"))
      (node (ref "SW38") (pin "2") (pinfunction "2_2") (pintype "passive"))
    )
    (net (code "83") (name "Net-(D39-A)") (class "Default")
      (node (ref "D39") (pin "1") (pinfunction "A_1") (pintype "passive"))
      (node (ref "SW39") (pin "2") (pinfunction "2_2") (pintype "passive"))
    )
    (net (code "84") (name "Net-(D40-A)") (class "Default")
      (node (ref "D40") (pin "1") (pinfunction "A_1") (pintype "passive"))
      (node (ref "SW40") (pin "2") (pinfunction "2_2") (pintype "passive"))
    )
    (net (code "85") (name "Net-(D41-A)") (class "Default")
      (node (ref "D41") (pin "1") (pinfunction "A_1") (pintype "passive"))
      (node (ref "SW41") (pin "2") (pinfunction "2_2") (pintype "passive"))
    )
    (net (code "86") (name "Net-(D42-A)") (class "Default")
      (node (ref "D42") (pin "1") (pinfunction "A_1") (pintype "passive"))
      (node (ref "SW42") (pin "2") (pinfunction "2_2") (pintype "passive"))
    )
    (net (code "87") (name "Net-(D43-A)") (class "Default")
      (node (ref "D43") (pin "1") (pinfunction "A_1") (pintype "passive"))
      (node (ref "SW43") (pin "2") (pinfunction "2_2") (pintype "passive"))
    )
    (net (code "88") (name "Net-(D44-A)") (class "Default")
      (node (ref "D44") (pin "1") (pinfunction "A_1") (pintype "passive"))
      (node (ref "SW44") (pin "2") (pinfunction "2_2") (pintype "passive"))
    )
    (net (code "89") (name "Net-(D45-A)") (class "Default")
      (node (ref "D45") (pin "1") (pinfunction "A_1") (pintype "passive"))
      (node (ref "SW45") (pin "2") (pinfunction "2_2") (pintype "passive"))
    )
    (net (code "90") (name "Net-(D46-A)") (class "Default")
      (node (ref "D46") (pin "1") (pinfunction "A_1") (pintype "passive"))
      (node (ref "SW46") (pin "2") (pinfunction "2_2") (pintype "passive"))
    )
    (net (code "91") (name "Net-(D47-A)") (class "Default")
      (node (ref "D47") (pin "1") (pinfunction "A_1") (pintype "passive"))
      (node (ref "SW47") (pin "2") (pinfunction "2_2") (pintype "passive"))
    )
    (net (code "92") (name "Net-(D48-A)") (class "Default")
      (node (ref "D48") (pin "1") (pinfunction "A_1") (pintype "passive"))
      (node (ref "SW48") (pin "2") (pinfunction "2_2") (pintype "passive"))
    )
    (net (code "93") (name "Net-(D49-A)") (class "Default")
      (node (ref "D49") (pin "1") (pinfunction "A_1") (pintype "passive"))
      (node (ref "SW49") (pin "2") (pinfunction "2_2") (pintype "passive"))
    )
    (net (code "94") (name "Net-(D50-A)") (class "Default")
      (node (ref "D50") (pin "1") (pinfunction "A_1") (pintype "passive"))
      (node (ref "SW50") (pin "2") (pinfunction "2_2") (pintype "passive"))
    )
    (net (code "95") (name "Net-(D51-A)") (class "Default")
      (node (ref "D51") (pin "1") (pinfunction "A_1") (pintype "passive"))
      (node (ref "SW51") (pin "2") (pinfunction "2_2") (pintype "passive"))
    )
    (net (code "96") (name "Net-(D52-A)") (class "Default")
      (node (ref "D52") (pin "1") (pinfunction "A_1") (pintype "passive"))
      (node (ref "SW52") (pin "2") (pinfunction "2_2") (pintype "passive"))
    )
    (net (code "97") (name "Net-(D53-A)") (class "Default")
      (node (ref "D53") (pin "1") (pinfunction "A_1") (pintype "passive"))
      (node (ref "SW53") (pin "2") (pinfunction "2_2") (pintype "passive"))
    )
    (net (code "98") (name "Net-(D54-A)") (class "Default")
      (node (ref "D54") (pin "1") (pinfunction "A_1") (pintype "passive"))
      (node (ref "SW54") (pin "2") (pinfunction "2_2") (pintype "passive"))
    )
    (net (code "99") (name "Net-(D55-A)") (class "Default")
      (node (ref "D55") (pin "1") (pinfunction "A_1") (pintype "passive"))
      (node (ref "SW55") (pin "2") (pinfunction "2_2") (pintype "passive"))
    )
    (net (code "100") (name "Net-(D56-A)") (class "Default")
      (node (ref "D56") (pin "1") (pinfunction "A_1") (pintype "passive"))
      (node (ref "SW56") (pin "2") (pinfunction "2_2") (pintype "passive"))
    )
    (net (code "101") (name "Net-(D57-A)") (class "Default")
      (node (ref "D57") (pin "1") (pinfunction "A_1") (pintype "passive"))
      (node (ref "SW57") (pin "2") (pinfunction "2_2") (pintype "passive"))
    )
    (net (code "102") (name "Net-(D58-A)") (class "Default")
      (node (ref "D58") (pin "1") (pinfunction "A_1") (pintype "passive"))
      (node (ref "SW58") (pin "2") (pinfunction "2_2") (pintype "passive"))
    )
    (net (code "103") (name "Net-(D59-A)") (class "Default")
      (node (ref "D59") (pin "1") (pinfunction "A_1") (pintype "passive"))
      (node (ref "SW59") (pin "2") (pinfunction "2_2") (pintype "passive"))
    )
    (net (code "104") (name "Net-(D60-A)") (class "Default")
      (node (ref "D60") (pin "1") (pinfunction "A_1") (pintype "passive"))
      (node (ref "SW60") (pin "2") (pinfunction "2_2") (pintype "passive"))
    )
    (net (code "105") (name "Net-(D61-A)") (class "Default")
      (node (ref "D61") (pin "1") (pinfunction "A_1") (pintype "passive"))
      (node (ref "SW61") (pin "2") (pinfunction "2_2") (pintype "passive"))
    )
    (net (code "106") (name "Net-(D62-A)") (class "Default")
      (node (ref "D62") (pin "1") (pinfunction "A_1") (pintype "passive"))
      (node (ref "SW62") (pin "2") (pinfunction "2_2") (pintype "passive"))
    )
    (net (code "107") (name "Net-(D63-A)") (class "Default")
      (node (ref "D63") (pin "1") (pinfunction "A_1") (pintype "passive"))
      (node (ref "SW63") (pin "2") (pinfunction "2_2") (pintype "passive"))
    )
    (net (code "108") (name "Net-(D64-A)") (class "Default")
      (node (ref "D64") (pin "1") (pinfunction "A_1") (pintype "passive"))
      (node (ref "SW64") (pin "2") (pinfunction "2_2") (pintype "passive"))
    )
    (net (code "109") (name "Net-(D65-A)") (class "Default")
      (node (ref "D65") (pin "1") (pinfunction "A_1") (pintype "passive"))
      (node (ref "SW65") (pin "2") (pinfunction "2_2") (pintype "passive"))
    )
    (net (code "110") (name "Net-(D66-A)") (class "Default")
      (node (ref "D66") (pin "1") (pinfunction "A_1") (pintype "passive"))
      (node (ref "SW66") (pin "2") (pinfunction "2_2") (pintype "passive"))
    )
    (net (code "111") (name "Net-(D67-A)") (class "Default")
      (node (ref "D67") (pin "1") (pinfunction "A_1") (pintype "passive"))
      (node (ref "SW67") (pin "2") (pinfunction "2_2") (pintype "passive"))
    )
    (net (code "112") (name "Net-(D68-A)") (class "Default")
      (node (ref "D68") (pin "1") (pinfunction "A_1") (pintype "passive"))
      (node (ref "SW68") (pin "2") (pinfunction "2_2") (pintype "passive"))
    )
    (net (code "113") (name "Net-(D69-A)") (class "Default")
      (node (ref "D69") (pin "1") (pinfunction "A_1") (pintype "passive"))
      (node (ref "SW69") (pin "2") (pinfunction "2_2") (pintype "passive"))
    )
    (net (code "114") (name "Net-(D70-A)") (class "Default")
      (node (ref "D70") (pin "1") (pinfunction "A_1") (pintype "passive"))
      (node (ref "SW70") (pin "2") (pinfunction "2_2") (pintype "passive"))
    )
    (net (code "115") (name "Net-(D71-A)") (class "Default")
      (node (ref "D71") (pin "1") (pinfunction "A_1") (pintype "passive"))
      (node (ref "SW71") (pin "2") (pinfunction "2_2") (pintype "passive"))
    )
    (net (code "116") (name "Net-(D72-A)") (class "Default")
      (node (ref "D72") (pin "1") (pinfunction "A_1") (pintype "passive"))
      (node (ref "SW72") (pin "2") (pinfunction "2_2") (pintype "passive"))
    )
    (net (code "117") (name "Net-(D73-A)") (class "Default")
      (node (ref "D73") (pin "1") (pinfunction "A_1") (pintype "passive"))
      (node (ref "SW73") (pin "2") (pinfunction "2_2") (pintype "passive"))
    )
    (net (code "118") (name "Net-(D74-A)") (class "Default")
      (node (ref "D74") (pin "1") (pinfunction "A_1") (pintype "passive"))
      (node (ref "SW74") (pin "2") (pinfunction "2_2") (pintype "passive"))
    )
    (net (code "119") (name "Net-(D75-A)") (class "Default")
      (node (ref "D75") (pin "1") (pinfunction "A_1") (pintype "passive"))
      (node (ref "SW75") (pin "2") (pinfunction "2_2") (pintype "passive"))
    )
    (net (code "120") (name "Net-(D76-A)") (class "Default")
      (node (ref "D76") (pin "1") (pinfunction "A_1") (pintype "passive"))
      (node (ref "SW76") (pin "2") (pinfunction "2_2") (pintype "passive"))
    )
    (net (code "121") (name "Net-(D77-A)") (class "Default")
      (node (ref "D77") (pin "1") (pinfunction "A_1") (pintype "passive"))
      (node (ref "SW77") (pin "2") (pinfunction "2_2") (pintype "passive"))
    )
    (net (code "122") (name "Net-(D78-A)") (class "Default")
      (node (ref "D78") (pin "1") (pinfunction "A_1") (pintype "passive"))
      (node (ref "SW78") (pin "2") (pinfunction "2_2") (pintype "passive"))
    )
    (net (code "123") (name "Net-(ENC1-CHANNEL_A)") (class "Default")
      (node (ref "ENC1") (pin "A") (pinfunction "CHANNEL_A_A") (pintype "passive"))
      (node (ref "R11") (pin "1") (pinfunction "1_1") (pintype "passive"))
      (node (ref "R8") (pin "2") (pinfunction "2_2") (pintype "passive"))
    )
    (net (code "124") (name "Net-(ENC1-CHANNEL_B)") (class "Default")
      (node (ref "ENC1") (pin "B") (pinfunction "CHANNEL_B_B") (pintype "passive"))
      (node (ref "R12") (pin "1") (pinfunction "1_1") (pintype "passive"))
      (node (ref "R9") (pin "2") (pinfunction "2_2") (pintype "passive"))
    )
    (net (code "125") (name "Net-(R1-Pad1)") (class "Default")
      (node (ref "R1") (pin "1") (pinfunction "1_1") (pintype "passive"))
      (node (ref "U1") (pin "B5") (pinfunction "B5_B5") (pintype "passive"))
    )
    (net (code "126") (name "Net-(R2-Pad2)") (class "Default")
      (node (ref "R2") (pin "2") (pinfunction "2_2") (pintype "passive"))
      (node (ref "U1") (pin "A5") (pinfunction "A5_A5") (pintype "passive"))
    )
    (net (code "127") (name "Net-(U3-USB_N)") (class "Default")
      (node (ref "R4") (pin "1") (pinfunction "1_1") (pintype "passive"))
      (node (ref "U3") (pin "46") (pinfunction "USB_N_46") (pintype "bidirectional"))
    )
    (net (code "128") (name "Net-(U3-USB_P)") (class "Default")
      (node (ref "R3") (pin "1") (pinfunction "1_1") (pintype "passive"))
      (node (ref "U3") (pin "47") (pinfunction "USB_P_47") (pintype "bidirectional"))
    )
    (net (code "129") (name "Net-(U3-XIN)") (class "Default")
      (node (ref "C15") (pin "2") (pinfunction "2_2") (pintype "passive"))
      (node (ref "U3") (pin "20") (pinfunction "XIN_20") (pintype "input"))
      (node (ref "Y1") (pin "1") (pinfunction "1_1") (pintype "passive"))
    )
    (net (code "130") (name "Net-(U3-XOUT)") (class "Default")
      (node (ref "R5") (pin "2") (pinfunction "2_2") (pintype "passive"))
      (node (ref "U3") (pin "21") (pinfunction "XOUT_21") (pintype "output"))
    )
    (net (code "131") (name "VUSB") (class "Default")
      (node (ref "C14") (pin "2") (pinfunction "2_2") (pintype "passive"))
      (node (ref "F1") (pin "1") (pinfunction "1_1") (pintype "passive"))
      (node (ref "U1") (pin "A4") (pinfunction "A4_A4") (pintype "passive"))
      (node (ref "U1") (pin "A9") (pinfunction "A9_A9") (pintype "passive"))
      (node (ref "U1") (pin "B4") (pinfunction "B4_B4") (pintype "passive"))
      (node (ref "U1") (pin "B9") (pinfunction "B9_B9") (pintype "passive"))
      (node (ref "U4") (pin "5") (pinfunction "VBUS_5") (pintype "passive"))
    )
    (net (code "132") (name "unconnected-(ENC1-MNT_1-Pad3)") (class "Default")
      (node (ref "ENC1") (pin "3") (pinfunction "MNT_1_3") (pintype "passive+no_connect"))
    )
    (net (code "133") (name "unconnected-(ENC1-MNT_2-Pad4)") (class "Default")
      (node (ref "ENC1") (pin "4") (pinfunction "MNT_2_4") (pintype "passive+no_connect"))
    )
    (net (code "134") (name "unconnected-(U1-PadA8)") (class "Default")
      (node (ref "U1") (pin "A8") (pinfunction "A8_A8") (pintype "passive+no_connect"))
    )
    (net (code "135") (name "unconnected-(U1-PadB8)") (class "Default")
      (node (ref "U1") (pin "B8") (pinfunction "B8_B8") (pintype "passive+no_connect"))
    )
    (net (code "136") (name "unconnected-(U1-PadMP1)") (class "Default")
      (node (ref "U1") (pin "MP1") (pinfunction "MP1_MP1") (pintype "passive+no_connect"))
    )
    (net (code "137") (name "unconnected-(U1-PadMP2)") (class "Default")
      (node (ref "U1") (pin "MP2") (pinfunction "MP2_MP2") (pintype "passive+no_connect"))
    )
    (net (code "138") (name "unconnected-(U1-PadMP3)") (class "Default")
      (node (ref "U1") (pin "MP3") (pinfunction "MP3_MP3") (pintype "passive+no_connect"))
    )
    (net (code "139") (name "unconnected-(U1-PadMP4)") (class "Default")
      (node (ref "U1") (pin "MP4") (pinfunction "MP4_MP4") (pintype "passive+no_connect"))
    )
    (net (code "140") (name "unconnected-(U3-GPIO26_{slash}_ADC0-Pad38)") (class "Default")
      (node (ref "U3") (pin "38") (pinfunction "GPIO26_/_ADC0_38") (pintype "bidirectional+no_connect"))
    )
    (net (code "141") (name "unconnected-(U3-GPIO27_{slash}_ADC1-Pad39)") (class "Default")
      (node (ref "U3") (pin "39") (pinfunction "GPIO27_/_ADC1_39") (pintype "bidirectional+no_connect"))
    )
    (net (code "142") (name "unconnected-(U3-GPIO28_{slash}_ADC2-Pad40)") (class "Default")
      (node (ref "U3") (pin "40") (pinfunction "GPIO28_/_ADC2_40") (pintype "bidirectional+no_connect"))
    )
    (net (code "143") (name "unconnected-(U3-GPIO29_{slash}_ADC3-Pad41)") (class "Default")
      (node (ref "U3") (pin "41") (pinfunction "GPIO29_/_ADC3_41") (pintype "bidirectional+no_connect"))
    )
  )
)
